# Linesensors.net
KiCad netlist of a schematic drawn in EAGLE
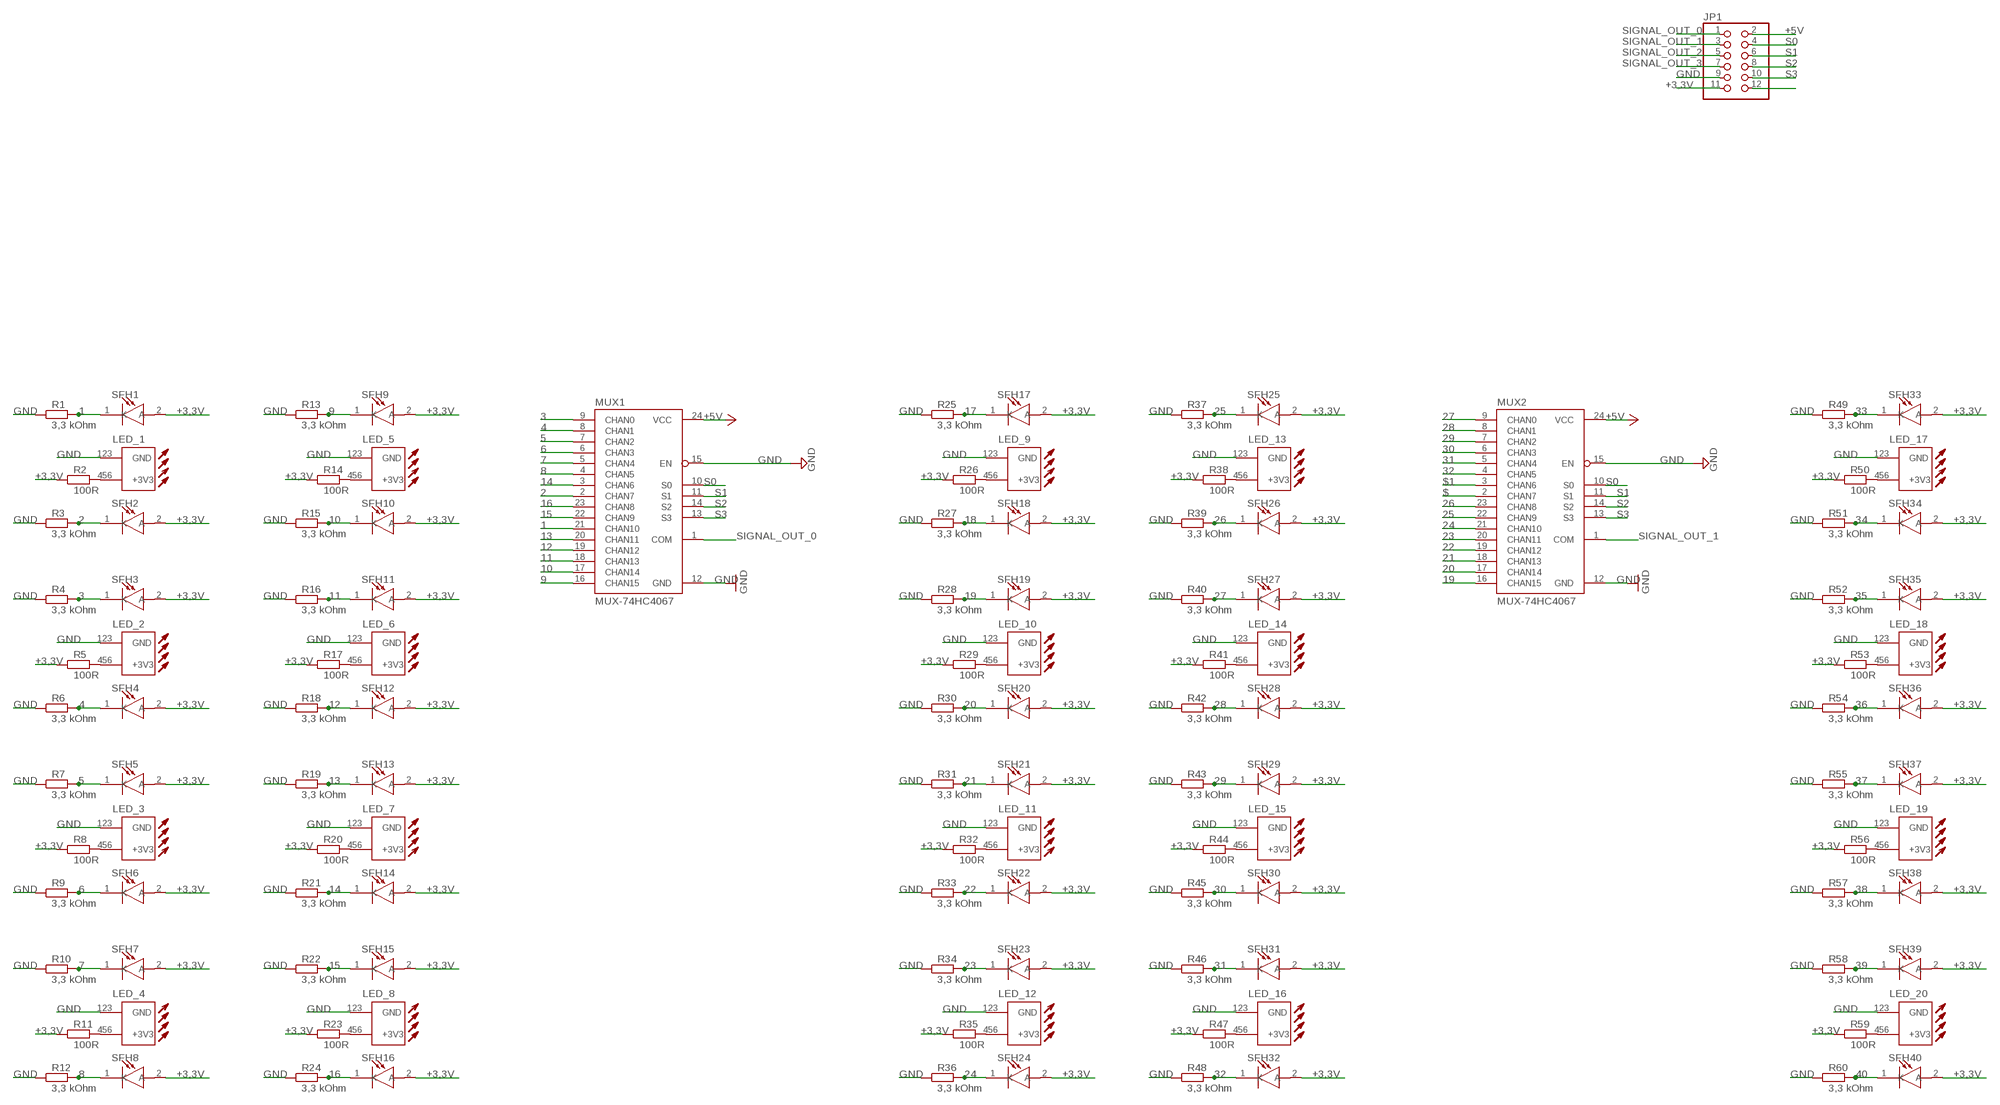
[diagram p0: schematic, sheet 1, part 1 of 2]
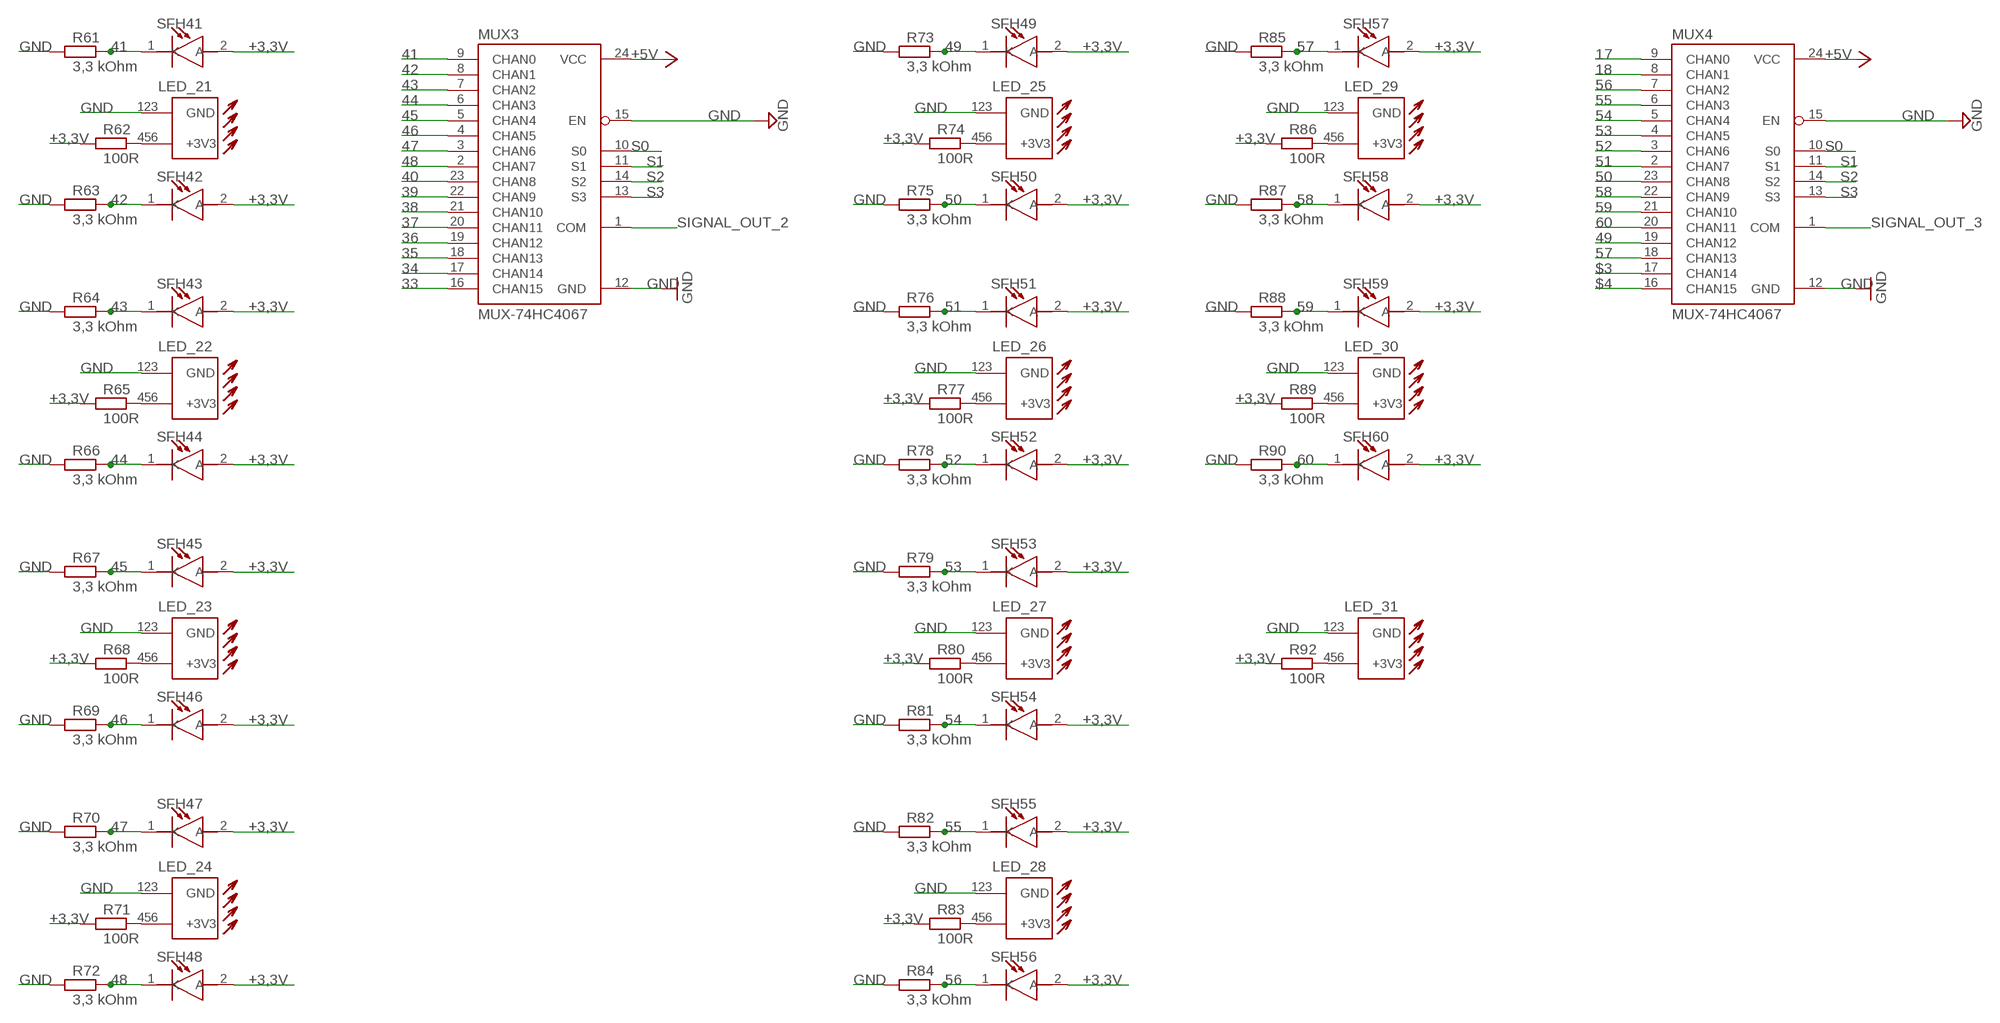
[diagram p1: schematic, sheet 1, part 2 of 2]

(export (version "E")
  (design (tool "Eeschema 10.0.6"))
  (components
    (comp (ref "JP1")
      (value "PINHD-2X6")
      (footprint "eagle-import:2X06")
      (libsource (lib "eagle-import") (part "PINHD-2X6"))
    )
    (comp (ref "LED_1")
      (value "RND135-00056LEDD")
      (footprint "eagle-import:LED")
      (libsource (lib "eagle-import") (part "RND135-00056LEDD"))
    )
    (comp (ref "LED_2")
      (value "RND135-00056LEDD")
      (footprint "eagle-import:LED")
      (libsource (lib "eagle-import") (part "RND135-00056LEDD"))
    )
    (comp (ref "LED_3")
      (value "RND135-00056LEDD")
      (footprint "eagle-import:LED")
      (libsource (lib "eagle-import") (part "RND135-00056LEDD"))
    )
    (comp (ref "LED_4")
      (value "RND135-00056LEDD")
      (footprint "eagle-import:LED")
      (libsource (lib "eagle-import") (part "RND135-00056LEDD"))
    )
    (comp (ref "LED_5")
      (value "RND135-00056LEDD")
      (footprint "eagle-import:LED")
      (libsource (lib "eagle-import") (part "RND135-00056LEDD"))
    )
    (comp (ref "LED_6")
      (value "RND135-00056LEDD")
      (footprint "eagle-import:LED")
      (libsource (lib "eagle-import") (part "RND135-00056LEDD"))
    )
    (comp (ref "LED_7")
      (value "RND135-00056LEDD")
      (footprint "eagle-import:LED")
      (libsource (lib "eagle-import") (part "RND135-00056LEDD"))
    )
    (comp (ref "LED_8")
      (value "RND135-00056LEDD")
      (footprint "eagle-import:LED")
      (libsource (lib "eagle-import") (part "RND135-00056LEDD"))
    )
    (comp (ref "LED_9")
      (value "RND135-00056LEDD")
      (footprint "eagle-import:LED")
      (libsource (lib "eagle-import") (part "RND135-00056LEDD"))
    )
    (comp (ref "LED_10")
      (value "RND135-00056LEDD")
      (footprint "eagle-import:LED")
      (libsource (lib "eagle-import") (part "RND135-00056LEDD"))
    )
    (comp (ref "LED_11")
      (value "RND135-00056LEDD")
      (footprint "eagle-import:LED")
      (libsource (lib "eagle-import") (part "RND135-00056LEDD"))
    )
    (comp (ref "LED_12")
      (value "RND135-00056LEDD")
      (footprint "eagle-import:LED")
      (libsource (lib "eagle-import") (part "RND135-00056LEDD"))
    )
    (comp (ref "LED_13")
      (value "RND135-00056LEDD")
      (footprint "eagle-import:LED")
      (libsource (lib "eagle-import") (part "RND135-00056LEDD"))
    )
    (comp (ref "LED_14")
      (value "RND135-00056LEDD")
      (footprint "eagle-import:LED")
      (libsource (lib "eagle-import") (part "RND135-00056LEDD"))
    )
    (comp (ref "LED_15")
      (value "RND135-00056LEDD")
      (footprint "eagle-import:LED")
      (libsource (lib "eagle-import") (part "RND135-00056LEDD"))
    )
    (comp (ref "LED_16")
      (value "RND135-00056LEDD")
      (footprint "eagle-import:LED")
      (libsource (lib "eagle-import") (part "RND135-00056LEDD"))
    )
    (comp (ref "LED_17")
      (value "RND135-00056LEDD")
      (footprint "eagle-import:LED")
      (libsource (lib "eagle-import") (part "RND135-00056LEDD"))
    )
    (comp (ref "LED_18")
      (value "RND135-00056LEDD")
      (footprint "eagle-import:LED")
      (libsource (lib "eagle-import") (part "RND135-00056LEDD"))
    )
    (comp (ref "LED_19")
      (value "RND135-00056LEDD")
      (footprint "eagle-import:LED")
      (libsource (lib "eagle-import") (part "RND135-00056LEDD"))
    )
    (comp (ref "LED_20")
      (value "RND135-00056LEDD")
      (footprint "eagle-import:LED")
      (libsource (lib "eagle-import") (part "RND135-00056LEDD"))
    )
    (comp (ref "LED_21")
      (value "RND135-00056LEDD")
      (footprint "eagle-import:LED")
      (libsource (lib "eagle-import") (part "RND135-00056LEDD"))
    )
    (comp (ref "LED_22")
      (value "RND135-00056LEDD")
      (footprint "eagle-import:LED")
      (libsource (lib "eagle-import") (part "RND135-00056LEDD"))
    )
    (comp (ref "LED_23")
      (value "RND135-00056LEDD")
      (footprint "eagle-import:LED")
      (libsource (lib "eagle-import") (part "RND135-00056LEDD"))
    )
    (comp (ref "LED_24")
      (value "RND135-00056LEDD")
      (footprint "eagle-import:LED")
      (libsource (lib "eagle-import") (part "RND135-00056LEDD"))
    )
    (comp (ref "LED_25")
      (value "RND135-00056LEDD")
      (footprint "eagle-import:LED")
      (libsource (lib "eagle-import") (part "RND135-00056LEDD"))
    )
    (comp (ref "LED_26")
      (value "RND135-00056LEDD")
      (footprint "eagle-import:LED")
      (libsource (lib "eagle-import") (part "RND135-00056LEDD"))
    )
    (comp (ref "LED_27")
      (value "RND135-00056LEDD")
      (footprint "eagle-import:LED")
      (libsource (lib "eagle-import") (part "RND135-00056LEDD"))
    )
    (comp (ref "LED_28")
      (value "RND135-00056LEDD")
      (footprint "eagle-import:LED")
      (libsource (lib "eagle-import") (part "RND135-00056LEDD"))
    )
    (comp (ref "LED_29")
      (value "RND135-00056LEDD")
      (footprint "eagle-import:LED")
      (libsource (lib "eagle-import") (part "RND135-00056LEDD"))
    )
    (comp (ref "LED_30")
      (value "RND135-00056LEDD")
      (footprint "eagle-import:LED")
      (libsource (lib "eagle-import") (part "RND135-00056LEDD"))
    )
    (comp (ref "LED_31")
      (value "RND135-00056LEDD")
      (footprint "eagle-import:LED")
      (libsource (lib "eagle-import") (part "RND135-00056LEDD"))
    )
    (comp (ref "MUX1")
      (value "MUX-74HC4067")
      (footprint "eagle-import:SSOP24")
      (libsource (lib "eagle-import") (part "MUX-74HC4067SMD"))
    )
    (comp (ref "MUX2")
      (value "MUX-74HC4067")
      (footprint "eagle-import:SSOP24")
      (libsource (lib "eagle-import") (part "MUX-74HC4067SMD"))
    )
    (comp (ref "MUX3")
      (value "MUX-74HC4067")
      (footprint "eagle-import:SSOP24")
      (libsource (lib "eagle-import") (part "MUX-74HC4067SMD"))
    )
    (comp (ref "MUX4")
      (value "MUX-74HC4067")
      (footprint "eagle-import:SSOP24")
      (libsource (lib "eagle-import") (part "MUX-74HC4067SMD"))
    )
    (comp (ref "R1")
      (value "3,3 kOhm")
      (footprint "eagle-import:R1206")
      (libsource (lib "eagle-import") (part "R-EU_R1206"))
    )
    (comp (ref "R2")
      (value "100R")
      (footprint "eagle-import:R1206")
      (libsource (lib "eagle-import") (part "R-EU_R1206"))
    )
    (comp (ref "R3")
      (value "3,3 kOhm")
      (footprint "eagle-import:R1206")
      (libsource (lib "eagle-import") (part "R-EU_R1206"))
    )
    (comp (ref "R4")
      (value "3,3 kOhm")
      (footprint "eagle-import:R1206")
      (libsource (lib "eagle-import") (part "R-EU_R1206"))
    )
    (comp (ref "R5")
      (value "100R")
      (footprint "eagle-import:R1206")
      (libsource (lib "eagle-import") (part "R-EU_R1206"))
    )
    (comp (ref "R6")
      (value "3,3 kOhm")
      (footprint "eagle-import:R1206")
      (libsource (lib "eagle-import") (part "R-EU_R1206"))
    )
    (comp (ref "R7")
      (value "3,3 kOhm")
      (footprint "eagle-import:R1206")
      (libsource (lib "eagle-import") (part "R-EU_R1206"))
    )
    (comp (ref "R8")
      (value "100R")
      (footprint "eagle-import:R1206")
      (libsource (lib "eagle-import") (part "R-EU_R1206"))
    )
    (comp (ref "R9")
      (value "3,3 kOhm")
      (footprint "eagle-import:R1206")
      (libsource (lib "eagle-import") (part "R-EU_R1206"))
    )
    (comp (ref "R10")
      (value "3,3 kOhm")
      (footprint "eagle-import:R1206")
      (libsource (lib "eagle-import") (part "R-EU_R1206"))
    )
    (comp (ref "R11")
      (value "100R")
      (footprint "eagle-import:R1206")
      (libsource (lib "eagle-import") (part "R-EU_R1206"))
    )
    (comp (ref "R12")
      (value "3,3 kOhm")
      (footprint "eagle-import:R1206")
      (libsource (lib "eagle-import") (part "R-EU_R1206"))
    )
    (comp (ref "R13")
      (value "3,3 kOhm")
      (footprint "eagle-import:R1206")
      (libsource (lib "eagle-import") (part "R-EU_R1206"))
    )
    (comp (ref "R14")
      (value "100R")
      (footprint "eagle-import:R1206")
      (libsource (lib "eagle-import") (part "R-EU_R1206"))
    )
    (comp (ref "R15")
      (value "3,3 kOhm")
      (footprint "eagle-import:R1206")
      (libsource (lib "eagle-import") (part "R-EU_R1206"))
    )
    (comp (ref "R16")
      (value "3,3 kOhm")
      (footprint "eagle-import:R1206")
      (libsource (lib "eagle-import") (part "R-EU_R1206"))
    )
    (comp (ref "R17")
      (value "100R")
      (footprint "eagle-import:R1206")
      (libsource (lib "eagle-import") (part "R-EU_R1206"))
    )
    (comp (ref "R18")
      (value "3,3 kOhm")
      (footprint "eagle-import:R1206")
      (libsource (lib "eagle-import") (part "R-EU_R1206"))
    )
    (comp (ref "R19")
      (value "3,3 kOhm")
      (footprint "eagle-import:R1206")
      (libsource (lib "eagle-import") (part "R-EU_R1206"))
    )
    (comp (ref "R20")
      (value "100R")
      (footprint "eagle-import:R1206")
      (libsource (lib "eagle-import") (part "R-EU_R1206"))
    )
    (comp (ref "R21")
      (value "3,3 kOhm")
      (footprint "eagle-import:R1206")
      (libsource (lib "eagle-import") (part "R-EU_R1206"))
    )
    (comp (ref "R22")
      (value "3,3 kOhm")
      (footprint "eagle-import:R1206")
      (libsource (lib "eagle-import") (part "R-EU_R1206"))
    )
    (comp (ref "R23")
      (value "100R")
      (footprint "eagle-import:R1206")
      (libsource (lib "eagle-import") (part "R-EU_R1206"))
    )
    (comp (ref "R24")
      (value "3,3 kOhm")
      (footprint "eagle-import:R1206")
      (libsource (lib "eagle-import") (part "R-EU_R1206"))
    )
    (comp (ref "R25")
      (value "3,3 kOhm")
      (footprint "eagle-import:R1206")
      (libsource (lib "eagle-import") (part "R-EU_R1206"))
    )
    (comp (ref "R26")
      (value "100R")
      (footprint "eagle-import:R1206")
      (libsource (lib "eagle-import") (part "R-EU_R1206"))
    )
    (comp (ref "R27")
      (value "3,3 kOhm")
      (footprint "eagle-import:R1206")
      (libsource (lib "eagle-import") (part "R-EU_R1206"))
    )
    (comp (ref "R28")
      (value "3,3 kOhm")
      (footprint "eagle-import:R1206")
      (libsource (lib "eagle-import") (part "R-EU_R1206"))
    )
    (comp (ref "R29")
      (value "100R")
      (footprint "eagle-import:R1206")
      (libsource (lib "eagle-import") (part "R-EU_R1206"))
    )
    (comp (ref "R30")
      (value "3,3 kOhm")
      (footprint "eagle-import:R1206")
      (libsource (lib "eagle-import") (part "R-EU_R1206"))
    )
    (comp (ref "R31")
      (value "3,3 kOhm")
      (footprint "eagle-import:R1206")
      (libsource (lib "eagle-import") (part "R-EU_R1206"))
    )
    (comp (ref "R32")
      (value "100R")
      (footprint "eagle-import:R1206")
      (libsource (lib "eagle-import") (part "R-EU_R1206"))
    )
    (comp (ref "R33")
      (value "3,3 kOhm")
      (footprint "eagle-import:R1206")
      (libsource (lib "eagle-import") (part "R-EU_R1206"))
    )
    (comp (ref "R34")
      (value "3,3 kOhm")
      (footprint "eagle-import:R1206")
      (libsource (lib "eagle-import") (part "R-EU_R1206"))
    )
    (comp (ref "R35")
      (value "100R")
      (footprint "eagle-import:R1206")
      (libsource (lib "eagle-import") (part "R-EU_R1206"))
    )
    (comp (ref "R36")
      (value "3,3 kOhm")
      (footprint "eagle-import:R1206")
      (libsource (lib "eagle-import") (part "R-EU_R1206"))
    )
    (comp (ref "R37")
      (value "3,3 kOhm")
      (footprint "eagle-import:R1206")
      (libsource (lib "eagle-import") (part "R-EU_R1206"))
    )
    (comp (ref "R38")
      (value "100R")
      (footprint "eagle-import:R1206")
      (libsource (lib "eagle-import") (part "R-EU_R1206"))
    )
    (comp (ref "R39")
      (value "3,3 kOhm")
      (footprint "eagle-import:R1206")
      (libsource (lib "eagle-import") (part "R-EU_R1206"))
    )
    (comp (ref "R40")
      (value "3,3 kOhm")
      (footprint "eagle-import:R1206")
      (libsource (lib "eagle-import") (part "R-EU_R1206"))
    )
    (comp (ref "R41")
      (value "100R")
      (footprint "eagle-import:R1206")
      (libsource (lib "eagle-import") (part "R-EU_R1206"))
    )
    (comp (ref "R42")
      (value "3,3 kOhm")
      (footprint "eagle-import:R1206")
      (libsource (lib "eagle-import") (part "R-EU_R1206"))
    )
    (comp (ref "R43")
      (value "3,3 kOhm")
      (footprint "eagle-import:R1206")
      (libsource (lib "eagle-import") (part "R-EU_R1206"))
    )
    (comp (ref "R44")
      (value "100R")
      (footprint "eagle-import:R1206")
      (libsource (lib "eagle-import") (part "R-EU_R1206"))
    )
    (comp (ref "R45")
      (value "3,3 kOhm")
      (footprint "eagle-import:R1206")
      (libsource (lib "eagle-import") (part "R-EU_R1206"))
    )
    (comp (ref "R46")
      (value "3,3 kOhm")
      (footprint "eagle-import:R1206")
      (libsource (lib "eagle-import") (part "R-EU_R1206"))
    )
    (comp (ref "R47")
      (value "100R")
      (footprint "eagle-import:R1206")
      (libsource (lib "eagle-import") (part "R-EU_R1206"))
    )
    (comp (ref "R48")
      (value "3,3 kOhm")
      (footprint "eagle-import:R1206")
      (libsource (lib "eagle-import") (part "R-EU_R1206"))
    )
    (comp (ref "R49")
      (value "3,3 kOhm")
      (footprint "eagle-import:R1206")
      (libsource (lib "eagle-import") (part "R-EU_R1206"))
    )
    (comp (ref "R50")
      (value "100R")
      (footprint "eagle-import:R1206")
      (libsource (lib "eagle-import") (part "R-EU_R1206"))
    )
    (comp (ref "R51")
      (value "3,3 kOhm")
      (footprint "eagle-import:R1206")
      (libsource (lib "eagle-import") (part "R-EU_R1206"))
    )
    (comp (ref "R52")
      (value "3,3 kOhm")
      (footprint "eagle-import:R1206")
      (libsource (lib "eagle-import") (part "R-EU_R1206"))
    )
    (comp (ref "R53")
      (value "100R")
      (footprint "eagle-import:R1206")
      (libsource (lib "eagle-import") (part "R-EU_R1206"))
    )
    (comp (ref "R54")
      (value "3,3 kOhm")
      (footprint "eagle-import:R1206")
      (libsource (lib "eagle-import") (part "R-EU_R1206"))
    )
    (comp (ref "R55")
      (value "3,3 kOhm")
      (footprint "eagle-import:R1206")
      (libsource (lib "eagle-import") (part "R-EU_R1206"))
    )
    (comp (ref "R56")
      (value "100R")
      (footprint "eagle-import:R1206")
      (libsource (lib "eagle-import") (part "R-EU_R1206"))
    )
    (comp (ref "R57")
      (value "3,3 kOhm")
      (footprint "eagle-import:R1206")
      (libsource (lib "eagle-import") (part "R-EU_R1206"))
    )
    (comp (ref "R58")
      (value "3,3 kOhm")
      (footprint "eagle-import:R1206")
      (libsource (lib "eagle-import") (part "R-EU_R1206"))
    )
    (comp (ref "R59")
      (value "100R")
      (footprint "eagle-import:R1206")
      (libsource (lib "eagle-import") (part "R-EU_R1206"))
    )
    (comp (ref "R60")
      (value "3,3 kOhm")
      (footprint "eagle-import:R1206")
      (libsource (lib "eagle-import") (part "R-EU_R1206"))
    )
    (comp (ref "R61")
      (value "3,3 kOhm")
      (footprint "eagle-import:R1206")
      (libsource (lib "eagle-import") (part "R-EU_R1206"))
    )
    (comp (ref "R62")
      (value "100R")
      (footprint "eagle-import:R1206")
      (libsource (lib "eagle-import") (part "R-EU_R1206"))
    )
    (comp (ref "R63")
      (value "3,3 kOhm")
      (footprint "eagle-import:R1206")
      (libsource (lib "eagle-import") (part "R-EU_R1206"))
    )
    (comp (ref "R64")
      (value "3,3 kOhm")
      (footprint "eagle-import:R1206")
      (libsource (lib "eagle-import") (part "R-EU_R1206"))
    )
    (comp (ref "R65")
      (value "100R")
      (footprint "eagle-import:R1206")
      (libsource (lib "eagle-import") (part "R-EU_R1206"))
    )
    (comp (ref "R66")
      (value "3,3 kOhm")
      (footprint "eagle-import:R1206")
      (libsource (lib "eagle-import") (part "R-EU_R1206"))
    )
    (comp (ref "R67")
      (value "3,3 kOhm")
      (footprint "eagle-import:R1206")
      (libsource (lib "eagle-import") (part "R-EU_R1206"))
    )
    (comp (ref "R68")
      (value "100R")
      (footprint "eagle-import:R1206")
      (libsource (lib "eagle-import") (part "R-EU_R1206"))
    )
    (comp (ref "R69")
      (value "3,3 kOhm")
      (footprint "eagle-import:R1206")
      (libsource (lib "eagle-import") (part "R-EU_R1206"))
    )
    (comp (ref "R70")
      (value "3,3 kOhm")
      (footprint "eagle-import:R1206")
      (libsource (lib "eagle-import") (part "R-EU_R1206"))
    )
    (comp (ref "R71")
      (value "100R")
      (footprint "eagle-import:R1206")
      (libsource (lib "eagle-import") (part "R-EU_R1206"))
    )
    (comp (ref "R72")
      (value "3,3 kOhm")
      (footprint "eagle-import:R1206")
      (libsource (lib "eagle-import") (part "R-EU_R1206"))
    )
    (comp (ref "R73")
      (value "3,3 kOhm")
      (footprint "eagle-import:R1206")
      (libsource (lib "eagle-import") (part "R-EU_R1206"))
    )
    (comp (ref "R74")
      (value "100R")
      (footprint "eagle-import:R1206")
      (libsource (lib "eagle-import") (part "R-EU_R1206"))
    )
    (comp (ref "R75")
      (value "3,3 kOhm")
      (footprint "eagle-import:R1206")
      (libsource (lib "eagle-import") (part "R-EU_R1206"))
    )
    (comp (ref "R76")
      (value "3,3 kOhm")
      (footprint "eagle-import:R1206")
      (libsource (lib "eagle-import") (part "R-EU_R1206"))
    )
    (comp (ref "R77")
      (value "100R")
      (footprint "eagle-import:R1206")
      (libsource (lib "eagle-import") (part "R-EU_R1206"))
    )
    (comp (ref "R78")
      (value "3,3 kOhm")
      (footprint "eagle-import:R1206")
      (libsource (lib "eagle-import") (part "R-EU_R1206"))
    )
    (comp (ref "R79")
      (value "3,3 kOhm")
      (footprint "eagle-import:R1206")
      (libsource (lib "eagle-import") (part "R-EU_R1206"))
    )
    (comp (ref "R80")
      (value "100R")
      (footprint "eagle-import:R1206")
      (libsource (lib "eagle-import") (part "R-EU_R1206"))
    )
    (comp (ref "R81")
      (value "3,3 kOhm")
      (footprint "eagle-import:R1206")
      (libsource (lib "eagle-import") (part "R-EU_R1206"))
    )
    (comp (ref "R82")
      (value "3,3 kOhm")
      (footprint "eagle-import:R1206")
      (libsource (lib "eagle-import") (part "R-EU_R1206"))
    )
    (comp (ref "R83")
      (value "100R")
      (footprint "eagle-import:R1206")
      (libsource (lib "eagle-import") (part "R-EU_R1206"))
    )
    (comp (ref "R84")
      (value "3,3 kOhm")
      (footprint "eagle-import:R1206")
      (libsource (lib "eagle-import") (part "R-EU_R1206"))
    )
    (comp (ref "R85")
      (value "3,3 kOhm")
      (footprint "eagle-import:R1206")
      (libsource (lib "eagle-import") (part "R-EU_R1206"))
    )
    (comp (ref "R86")
      (value "100R")
      (footprint "eagle-import:R1206")
      (libsource (lib "eagle-import") (part "R-EU_R1206"))
    )
    (comp (ref "R87")
      (value "3,3 kOhm")
      (footprint "eagle-import:R1206")
      (libsource (lib "eagle-import") (part "R-EU_R1206"))
    )
    (comp (ref "R88")
      (value "3,3 kOhm")
      (footprint "eagle-import:R1206")
      (libsource (lib "eagle-import") (part "R-EU_R1206"))
    )
    (comp (ref "R89")
      (value "100R")
      (footprint "eagle-import:R1206")
      (libsource (lib "eagle-import") (part "R-EU_R1206"))
    )
    (comp (ref "R90")
      (value "3,3 kOhm")
      (footprint "eagle-import:R1206")
      (libsource (lib "eagle-import") (part "R-EU_R1206"))
    )
    (comp (ref "R92")
      (value "100R")
      (footprint "eagle-import:R1206")
      (libsource (lib "eagle-import") (part "R-EU_R1206"))
    )
    (comp (ref "SFH1")
      (value "SFH_3716")
      (footprint "eagle-import:LEDC2012X89N")
      (fields
        (field (name "MANUFACTURER_PART_NUMBER") "SFH 3716")
        (field (name "MOUSER_PART_NUMBER") "720-SFH3716")
        (field (name "RS_PART_NUMBER") "1115952P")
      )
      (libsource (lib "eagle-import") (part "SFH_3716"))
    )
    (comp (ref "SFH2")
      (value "SFH_3716")
      (footprint "eagle-import:LEDC2012X89N")
      (fields
        (field (name "MANUFACTURER_PART_NUMBER") "SFH 3716")
        (field (name "MOUSER_PART_NUMBER") "720-SFH3716")
        (field (name "RS_PART_NUMBER") "1115952P")
      )
      (libsource (lib "eagle-import") (part "SFH_3716"))
    )
    (comp (ref "SFH3")
      (value "SFH_3716")
      (footprint "eagle-import:LEDC2012X89N")
      (fields
        (field (name "MANUFACTURER_PART_NUMBER") "SFH 3716")
        (field (name "MOUSER_PART_NUMBER") "720-SFH3716")
        (field (name "RS_PART_NUMBER") "1115952P")
      )
      (libsource (lib "eagle-import") (part "SFH_3716"))
    )
    (comp (ref "SFH4")
      (value "SFH_3716")
      (footprint "eagle-import:LEDC2012X89N")
      (fields
        (field (name "MANUFACTURER_PART_NUMBER") "SFH 3716")
        (field (name "MOUSER_PART_NUMBER") "720-SFH3716")
        (field (name "RS_PART_NUMBER") "1115952P")
      )
      (libsource (lib "eagle-import") (part "SFH_3716"))
    )
    (comp (ref "SFH5")
      (value "SFH_3716")
      (footprint "eagle-import:LEDC2012X89N")
      (fields
        (field (name "MANUFACTURER_PART_NUMBER") "SFH 3716")
        (field (name "MOUSER_PART_NUMBER") "720-SFH3716")
        (field (name "RS_PART_NUMBER") "1115952P")
      )
      (libsource (lib "eagle-import") (part "SFH_3716"))
    )
    (comp (ref "SFH6")
      (value "SFH_3716")
      (footprint "eagle-import:LEDC2012X89N")
      (fields
        (field (name "MANUFACTURER_PART_NUMBER") "SFH 3716")
        (field (name "MOUSER_PART_NUMBER") "720-SFH3716")
        (field (name "RS_PART_NUMBER") "1115952P")
      )
      (libsource (lib "eagle-import") (part "SFH_3716"))
    )
    (comp (ref "SFH7")
      (value "SFH_3716")
      (footprint "eagle-import:LEDC2012X89N")
      (fields
        (field (name "MANUFACTURER_PART_NUMBER") "SFH 3716")
        (field (name "MOUSER_PART_NUMBER") "720-SFH3716")
        (field (name "RS_PART_NUMBER") "1115952P")
      )
      (libsource (lib "eagle-import") (part "SFH_3716"))
    )
    (comp (ref "SFH8")
      (value "SFH_3716")
      (footprint "eagle-import:LEDC2012X89N")
      (fields
        (field (name "MANUFACTURER_PART_NUMBER") "SFH 3716")
        (field (name "MOUSER_PART_NUMBER") "720-SFH3716")
        (field (name "RS_PART_NUMBER") "1115952P")
      )
      (libsource (lib "eagle-import") (part "SFH_3716"))
    )
    (comp (ref "SFH9")
      (value "SFH_3716")
      (footprint "eagle-import:LEDC2012X89N")
      (fields
        (field (name "MANUFACTURER_PART_NUMBER") "SFH 3716")
        (field (name "MOUSER_PART_NUMBER") "720-SFH3716")
        (field (name "RS_PART_NUMBER") "1115952P")
      )
      (libsource (lib "eagle-import") (part "SFH_3716"))
    )
    (comp (ref "SFH10")
      (value "SFH_3716")
      (footprint "eagle-import:LEDC2012X89N")
      (fields
        (field (name "MANUFACTURER_PART_NUMBER") "SFH 3716")
        (field (name "MOUSER_PART_NUMBER") "720-SFH3716")
        (field (name "RS_PART_NUMBER") "1115952P")
      )
      (libsource (lib "eagle-import") (part "SFH_3716"))
    )
    (comp (ref "SFH11")
      (value "SFH_3716")
      (footprint "eagle-import:LEDC2012X89N")
      (fields
        (field (name "MANUFACTURER_PART_NUMBER") "SFH 3716")
        (field (name "MOUSER_PART_NUMBER") "720-SFH3716")
        (field (name "RS_PART_NUMBER") "1115952P")
      )
      (libsource (lib "eagle-import") (part "SFH_3716"))
    )
    (comp (ref "SFH12")
      (value "SFH_3716")
      (footprint "eagle-import:LEDC2012X89N")
      (fields
        (field (name "MANUFACTURER_PART_NUMBER") "SFH 3716")
        (field (name "MOUSER_PART_NUMBER") "720-SFH3716")
        (field (name "RS_PART_NUMBER") "1115952P")
      )
      (libsource (lib "eagle-import") (part "SFH_3716"))
    )
    (comp (ref "SFH13")
      (value "SFH_3716")
      (footprint "eagle-import:LEDC2012X89N")
      (fields
        (field (name "MANUFACTURER_PART_NUMBER") "SFH 3716")
        (field (name "MOUSER_PART_NUMBER") "720-SFH3716")
        (field (name "RS_PART_NUMBER") "1115952P")
      )
      (libsource (lib "eagle-import") (part "SFH_3716"))
    )
    (comp (ref "SFH14")
      (value "SFH_3716")
      (footprint "eagle-import:LEDC2012X89N")
      (fields
        (field (name "MANUFACTURER_PART_NUMBER") "SFH 3716")
        (field (name "MOUSER_PART_NUMBER") "720-SFH3716")
        (field (name "RS_PART_NUMBER") "1115952P")
      )
      (libsource (lib "eagle-import") (part "SFH_3716"))
    )
    (comp (ref "SFH15")
      (value "SFH_3716")
      (footprint "eagle-import:LEDC2012X89N")
      (fields
        (field (name "MANUFACTURER_PART_NUMBER") "SFH 3716")
        (field (name "MOUSER_PART_NUMBER") "720-SFH3716")
        (field (name "RS_PART_NUMBER") "1115952P")
      )
      (libsource (lib "eagle-import") (part "SFH_3716"))
    )
    (comp (ref "SFH16")
      (value "SFH_3716")
      (footprint "eagle-import:LEDC2012X89N")
      (fields
        (field (name "MANUFACTURER_PART_NUMBER") "SFH 3716")
        (field (name "MOUSER_PART_NUMBER") "720-SFH3716")
        (field (name "RS_PART_NUMBER") "1115952P")
      )
      (libsource (lib "eagle-import") (part "SFH_3716"))
    )
    (comp (ref "SFH17")
      (value "SFH_3716")
      (footprint "eagle-import:LEDC2012X89N")
      (fields
        (field (name "MANUFACTURER_PART_NUMBER") "SFH 3716")
        (field (name "MOUSER_PART_NUMBER") "720-SFH3716")
        (field (name "RS_PART_NUMBER") "1115952P")
      )
      (libsource (lib "eagle-import") (part "SFH_3716"))
    )
    (comp (ref "SFH18")
      (value "SFH_3716")
      (footprint "eagle-import:LEDC2012X89N")
      (fields
        (field (name "MANUFACTURER_PART_NUMBER") "SFH 3716")
        (field (name "MOUSER_PART_NUMBER") "720-SFH3716")
        (field (name "RS_PART_NUMBER") "1115952P")
      )
      (libsource (lib "eagle-import") (part "SFH_3716"))
    )
    (comp (ref "SFH19")
      (value "SFH_3716")
      (footprint "eagle-import:LEDC2012X89N")
      (fields
        (field (name "MANUFACTURER_PART_NUMBER") "SFH 3716")
        (field (name "MOUSER_PART_NUMBER") "720-SFH3716")
        (field (name "RS_PART_NUMBER") "1115952P")
      )
      (libsource (lib "eagle-import") (part "SFH_3716"))
    )
    (comp (ref "SFH20")
      (value "SFH_3716")
      (footprint "eagle-import:LEDC2012X89N")
      (fields
        (field (name "MANUFACTURER_PART_NUMBER") "SFH 3716")
        (field (name "MOUSER_PART_NUMBER") "720-SFH3716")
        (field (name "RS_PART_NUMBER") "1115952P")
      )
      (libsource (lib "eagle-import") (part "SFH_3716"))
    )
    (comp (ref "SFH21")
      (value "SFH_3716")
      (footprint "eagle-import:LEDC2012X89N")
      (fields
        (field (name "MANUFACTURER_PART_NUMBER") "SFH 3716")
        (field (name "MOUSER_PART_NUMBER") "720-SFH3716")
        (field (name "RS_PART_NUMBER") "1115952P")
      )
      (libsource (lib "eagle-import") (part "SFH_3716"))
    )
    (comp (ref "SFH22")
      (value "SFH_3716")
      (footprint "eagle-import:LEDC2012X89N")
      (fields
        (field (name "MANUFACTURER_PART_NUMBER") "SFH 3716")
        (field (name "MOUSER_PART_NUMBER") "720-SFH3716")
        (field (name "RS_PART_NUMBER") "1115952P")
      )
      (libsource (lib "eagle-import") (part "SFH_3716"))
    )
    (comp (ref "SFH23")
      (value "SFH_3716")
      (footprint "eagle-import:LEDC2012X89N")
      (fields
        (field (name "MANUFACTURER_PART_NUMBER") "SFH 3716")
        (field (name "MOUSER_PART_NUMBER") "720-SFH3716")
        (field (name "RS_PART_NUMBER") "1115952P")
      )
      (libsource (lib "eagle-import") (part "SFH_3716"))
    )
    (comp (ref "SFH24")
      (value "SFH_3716")
      (footprint "eagle-import:LEDC2012X89N")
      (fields
        (field (name "MANUFACTURER_PART_NUMBER") "SFH 3716")
        (field (name "MOUSER_PART_NUMBER") "720-SFH3716")
        (field (name "RS_PART_NUMBER") "1115952P")
      )
      (libsource (lib "eagle-import") (part "SFH_3716"))
    )
    (comp (ref "SFH25")
      (value "SFH_3716")
      (footprint "eagle-import:LEDC2012X89N")
      (fields
        (field (name "MANUFACTURER_PART_NUMBER") "SFH 3716")
        (field (name "MOUSER_PART_NUMBER") "720-SFH3716")
        (field (name "RS_PART_NUMBER") "1115952P")
      )
      (libsource (lib "eagle-import") (part "SFH_3716"))
    )
    (comp (ref "SFH26")
      (value "SFH_3716")
      (footprint "eagle-import:LEDC2012X89N")
      (fields
        (field (name "MANUFACTURER_PART_NUMBER") "SFH 3716")
        (field (name "MOUSER_PART_NUMBER") "720-SFH3716")
        (field (name "RS_PART_NUMBER") "1115952P")
      )
      (libsource (lib "eagle-import") (part "SFH_3716"))
    )
    (comp (ref "SFH27")
      (value "SFH_3716")
      (footprint "eagle-import:LEDC2012X89N")
      (fields
        (field (name "MANUFACTURER_PART_NUMBER") "SFH 3716")
        (field (name "MOUSER_PART_NUMBER") "720-SFH3716")
        (field (name "RS_PART_NUMBER") "1115952P")
      )
      (libsource (lib "eagle-import") (part "SFH_3716"))
    )
    (comp (ref "SFH28")
      (value "SFH_3716")
      (footprint "eagle-import:LEDC2012X89N")
      (fields
        (field (name "MANUFACTURER_PART_NUMBER") "SFH 3716")
        (field (name "MOUSER_PART_NUMBER") "720-SFH3716")
        (field (name "RS_PART_NUMBER") "1115952P")
      )
      (libsource (lib "eagle-import") (part "SFH_3716"))
    )
    (comp (ref "SFH29")
      (value "SFH_3716")
      (footprint "eagle-import:LEDC2012X89N")
      (fields
        (field (name "MANUFACTURER_PART_NUMBER") "SFH 3716")
        (field (name "MOUSER_PART_NUMBER") "720-SFH3716")
        (field (name "RS_PART_NUMBER") "1115952P")
      )
      (libsource (lib "eagle-import") (part "SFH_3716"))
    )
    (comp (ref "SFH30")
      (value "SFH_3716")
      (footprint "eagle-import:LEDC2012X89N")
      (fields
        (field (name "MANUFACTURER_PART_NUMBER") "SFH 3716")
        (field (name "MOUSER_PART_NUMBER") "720-SFH3716")
        (field (name "RS_PART_NUMBER") "1115952P")
      )
      (libsource (lib "eagle-import") (part "SFH_3716"))
    )
    (comp (ref "SFH31")
      (value "SFH_3716")
      (footprint "eagle-import:LEDC2012X89N")
      (fields
        (field (name "MANUFACTURER_PART_NUMBER") "SFH 3716")
        (field (name "MOUSER_PART_NUMBER") "720-SFH3716")
        (field (name "RS_PART_NUMBER") "1115952P")
      )
      (libsource (lib "eagle-import") (part "SFH_3716"))
    )
    (comp (ref "SFH32")
      (value "SFH_3716")
      (footprint "eagle-import:LEDC2012X89N")
      (fields
        (field (name "MANUFACTURER_PART_NUMBER") "SFH 3716")
        (field (name "MOUSER_PART_NUMBER") "720-SFH3716")
        (field (name "RS_PART_NUMBER") "1115952P")
      )
      (libsource (lib "eagle-import") (part "SFH_3716"))
    )
    (comp (ref "SFH33")
      (value "SFH_3716")
      (footprint "eagle-import:LEDC2012X89N")
      (fields
        (field (name "MANUFACTURER_PART_NUMBER") "SFH 3716")
        (field (name "MOUSER_PART_NUMBER") "720-SFH3716")
        (field (name "RS_PART_NUMBER") "1115952P")
      )
      (libsource (lib "eagle-import") (part "SFH_3716"))
    )
    (comp (ref "SFH34")
      (value "SFH_3716")
      (footprint "eagle-import:LEDC2012X89N")
      (fields
        (field (name "MANUFACTURER_PART_NUMBER") "SFH 3716")
        (field (name "MOUSER_PART_NUMBER") "720-SFH3716")
        (field (name "RS_PART_NUMBER") "1115952P")
      )
      (libsource (lib "eagle-import") (part "SFH_3716"))
    )
    (comp (ref "SFH35")
      (value "SFH_3716")
      (footprint "eagle-import:LEDC2012X89N")
      (fields
        (field (name "MANUFACTURER_PART_NUMBER") "SFH 3716")
        (field (name "MOUSER_PART_NUMBER") "720-SFH3716")
        (field (name "RS_PART_NUMBER") "1115952P")
      )
      (libsource (lib "eagle-import") (part "SFH_3716"))
    )
    (comp (ref "SFH36")
      (value "SFH_3716")
      (footprint "eagle-import:LEDC2012X89N")
      (fields
        (field (name "MANUFACTURER_PART_NUMBER") "SFH 3716")
        (field (name "MOUSER_PART_NUMBER") "720-SFH3716")
        (field (name "RS_PART_NUMBER") "1115952P")
      )
      (libsource (lib "eagle-import") (part "SFH_3716"))
    )
    (comp (ref "SFH37")
      (value "SFH_3716")
      (footprint "eagle-import:LEDC2012X89N")
      (fields
        (field (name "MANUFACTURER_PART_NUMBER") "SFH 3716")
        (field (name "MOUSER_PART_NUMBER") "720-SFH3716")
        (field (name "RS_PART_NUMBER") "1115952P")
      )
      (libsource (lib "eagle-import") (part "SFH_3716"))
    )
    (comp (ref "SFH38")
      (value "SFH_3716")
      (footprint "eagle-import:LEDC2012X89N")
      (fields
        (field (name "MANUFACTURER_PART_NUMBER") "SFH 3716")
        (field (name "MOUSER_PART_NUMBER") "720-SFH3716")
        (field (name "RS_PART_NUMBER") "1115952P")
      )
      (libsource (lib "eagle-import") (part "SFH_3716"))
    )
    (comp (ref "SFH39")
      (value "SFH_3716")
      (footprint "eagle-import:LEDC2012X89N")
      (fields
        (field (name "MANUFACTURER_PART_NUMBER") "SFH 3716")
        (field (name "MOUSER_PART_NUMBER") "720-SFH3716")
        (field (name "RS_PART_NUMBER") "1115952P")
      )
      (libsource (lib "eagle-import") (part "SFH_3716"))
    )
    (comp (ref "SFH40")
      (value "SFH_3716")
      (footprint "eagle-import:LEDC2012X89N")
      (fields
        (field (name "MANUFACTURER_PART_NUMBER") "SFH 3716")
        (field (name "MOUSER_PART_NUMBER") "720-SFH3716")
        (field (name "RS_PART_NUMBER") "1115952P")
      )
      (libsource (lib "eagle-import") (part "SFH_3716"))
    )
    (comp (ref "SFH41")
      (value "SFH_3716")
      (footprint "eagle-import:LEDC2012X89N")
      (fields
        (field (name "MANUFACTURER_PART_NUMBER") "SFH 3716")
        (field (name "MOUSER_PART_NUMBER") "720-SFH3716")
        (field (name "RS_PART_NUMBER") "1115952P")
      )
      (libsource (lib "eagle-import") (part "SFH_3716"))
    )
    (comp (ref "SFH42")
      (value "SFH_3716")
      (footprint "eagle-import:LEDC2012X89N")
      (fields
        (field (name "MANUFACTURER_PART_NUMBER") "SFH 3716")
        (field (name "MOUSER_PART_NUMBER") "720-SFH3716")
        (field (name "RS_PART_NUMBER") "1115952P")
      )
      (libsource (lib "eagle-import") (part "SFH_3716"))
    )
    (comp (ref "SFH43")
      (value "SFH_3716")
      (footprint "eagle-import:LEDC2012X89N")
      (fields
        (field (name "MANUFACTURER_PART_NUMBER") "SFH 3716")
        (field (name "MOUSER_PART_NUMBER") "720-SFH3716")
        (field (name "RS_PART_NUMBER") "1115952P")
      )
      (libsource (lib "eagle-import") (part "SFH_3716"))
    )
    (comp (ref "SFH44")
      (value "SFH_3716")
      (footprint "eagle-import:LEDC2012X89N")
      (fields
        (field (name "MANUFACTURER_PART_NUMBER") "SFH 3716")
        (field (name "MOUSER_PART_NUMBER") "720-SFH3716")
        (field (name "RS_PART_NUMBER") "1115952P")
      )
      (libsource (lib "eagle-import") (part "SFH_3716"))
    )
    (comp (ref "SFH45")
      (value "SFH_3716")
      (footprint "eagle-import:LEDC2012X89N")
      (fields
        (field (name "MANUFACTURER_PART_NUMBER") "SFH 3716")
        (field (name "MOUSER_PART_NUMBER") "720-SFH3716")
        (field (name "RS_PART_NUMBER") "1115952P")
      )
      (libsource (lib "eagle-import") (part "SFH_3716"))
    )
    (comp (ref "SFH46")
      (value "SFH_3716")
      (footprint "eagle-import:LEDC2012X89N")
      (fields
        (field (name "MANUFACTURER_PART_NUMBER") "SFH 3716")
        (field (name "MOUSER_PART_NUMBER") "720-SFH3716")
        (field (name "RS_PART_NUMBER") "1115952P")
      )
      (libsource (lib "eagle-import") (part "SFH_3716"))
    )
    (comp (ref "SFH47")
      (value "SFH_3716")
      (footprint "eagle-import:LEDC2012X89N")
      (fields
        (field (name "MANUFACTURER_PART_NUMBER") "SFH 3716")
        (field (name "MOUSER_PART_NUMBER") "720-SFH3716")
        (field (name "RS_PART_NUMBER") "1115952P")
      )
      (libsource (lib "eagle-import") (part "SFH_3716"))
    )
    (comp (ref "SFH48")
      (value "SFH_3716")
      (footprint "eagle-import:LEDC2012X89N")
      (fields
        (field (name "MANUFACTURER_PART_NUMBER") "SFH 3716")
        (field (name "MOUSER_PART_NUMBER") "720-SFH3716")
        (field (name "RS_PART_NUMBER") "1115952P")
      )
      (libsource (lib "eagle-import") (part "SFH_3716"))
    )
    (comp (ref "SFH49")
      (value "SFH_3716")
      (footprint "eagle-import:LEDC2012X89N")
      (fields
        (field (name "MANUFACTURER_PART_NUMBER") "SFH 3716")
        (field (name "MOUSER_PART_NUMBER") "720-SFH3716")
        (field (name "RS_PART_NUMBER") "1115952P")
      )
      (libsource (lib "eagle-import") (part "SFH_3716"))
    )
    (comp (ref "SFH50")
      (value "SFH_3716")
      (footprint "eagle-import:LEDC2012X89N")
      (fields
        (field (name "MANUFACTURER_PART_NUMBER") "SFH 3716")
        (field (name "MOUSER_PART_NUMBER") "720-SFH3716")
        (field (name "RS_PART_NUMBER") "1115952P")
      )
      (libsource (lib "eagle-import") (part "SFH_3716"))
    )
    (comp (ref "SFH51")
      (value "SFH_3716")
      (footprint "eagle-import:LEDC2012X89N")
      (fields
        (field (name "MANUFACTURER_PART_NUMBER") "SFH 3716")
        (field (name "MOUSER_PART_NUMBER") "720-SFH3716")
        (field (name "RS_PART_NUMBER") "1115952P")
      )
      (libsource (lib "eagle-import") (part "SFH_3716"))
    )
    (comp (ref "SFH52")
      (value "SFH_3716")
      (footprint "eagle-import:LEDC2012X89N")
      (fields
        (field (name "MANUFACTURER_PART_NUMBER") "SFH 3716")
        (field (name "MOUSER_PART_NUMBER") "720-SFH3716")
        (field (name "RS_PART_NUMBER") "1115952P")
      )
      (libsource (lib "eagle-import") (part "SFH_3716"))
    )
    (comp (ref "SFH53")
      (value "SFH_3716")
      (footprint "eagle-import:LEDC2012X89N")
      (fields
        (field (name "MANUFACTURER_PART_NUMBER") "SFH 3716")
        (field (name "MOUSER_PART_NUMBER") "720-SFH3716")
        (field (name "RS_PART_NUMBER") "1115952P")
      )
      (libsource (lib "eagle-import") (part "SFH_3716"))
    )
    (comp (ref "SFH54")
      (value "SFH_3716")
      (footprint "eagle-import:LEDC2012X89N")
      (fields
        (field (name "MANUFACTURER_PART_NUMBER") "SFH 3716")
        (field (name "MOUSER_PART_NUMBER") "720-SFH3716")
        (field (name "RS_PART_NUMBER") "1115952P")
      )
      (libsource (lib "eagle-import") (part "SFH_3716"))
    )
    (comp (ref "SFH55")
      (value "SFH_3716")
      (footprint "eagle-import:LEDC2012X89N")
      (fields
        (field (name "MANUFACTURER_PART_NUMBER") "SFH 3716")
        (field (name "MOUSER_PART_NUMBER") "720-SFH3716")
        (field (name "RS_PART_NUMBER") "1115952P")
      )
      (libsource (lib "eagle-import") (part "SFH_3716"))
    )
    (comp (ref "SFH56")
      (value "SFH_3716")
      (footprint "eagle-import:LEDC2012X89N")
      (fields
        (field (name "MANUFACTURER_PART_NUMBER") "SFH 3716")
        (field (name "MOUSER_PART_NUMBER") "720-SFH3716")
        (field (name "RS_PART_NUMBER") "1115952P")
      )
      (libsource (lib "eagle-import") (part "SFH_3716"))
    )
    (comp (ref "SFH57")
      (value "SFH_3716")
      (footprint "eagle-import:LEDC2012X89N")
      (fields
        (field (name "MANUFACTURER_PART_NUMBER") "SFH 3716")
        (field (name "MOUSER_PART_NUMBER") "720-SFH3716")
        (field (name "RS_PART_NUMBER") "1115952P")
      )
      (libsource (lib "eagle-import") (part "SFH_3716"))
    )
    (comp (ref "SFH58")
      (value "SFH_3716")
      (footprint "eagle-import:LEDC2012X89N")
      (fields
        (field (name "MANUFACTURER_PART_NUMBER") "SFH 3716")
        (field (name "MOUSER_PART_NUMBER") "720-SFH3716")
        (field (name "RS_PART_NUMBER") "1115952P")
      )
      (libsource (lib "eagle-import") (part "SFH_3716"))
    )
    (comp (ref "SFH59")
      (value "SFH_3716")
      (footprint "eagle-import:LEDC2012X89N")
      (fields
        (field (name "MANUFACTURER_PART_NUMBER") "SFH 3716")
        (field (name "MOUSER_PART_NUMBER") "720-SFH3716")
        (field (name "RS_PART_NUMBER") "1115952P")
      )
      (libsource (lib "eagle-import") (part "SFH_3716"))
    )
    (comp (ref "SFH60")
      (value "SFH_3716")
      (footprint "eagle-import:LEDC2012X89N")
      (fields
        (field (name "MANUFACTURER_PART_NUMBER") "SFH 3716")
        (field (name "MOUSER_PART_NUMBER") "720-SFH3716")
        (field (name "RS_PART_NUMBER") "1115952P")
      )
      (libsource (lib "eagle-import") (part "SFH_3716"))
    )
  )
  (nets
    (net (code "1") (name "+5V") (class "Default")
      (node (ref "JP1") (pin "2") (pinfunction "2_2") (pintype "passive"))
      (node (ref "MUX1") (pin "24") (pinfunction "VCC_24") (pintype "bidirectional"))
      (node (ref "MUX2") (pin "24") (pinfunction "VCC_24") (pintype "bidirectional"))
      (node (ref "MUX3") (pin "24") (pinfunction "VCC_24") (pintype "bidirectional"))
      (node (ref "MUX4") (pin "24") (pinfunction "VCC_24") (pintype "bidirectional"))
    )
    (net (code "2") (name "/$") (class "Default")
      (node (ref "MUX2") (pin "2") (pinfunction "CHAN7_2") (pintype "bidirectional"))
    )
    (net (code "3") (name "/$1") (class "Default")
      (node (ref "MUX2") (pin "3") (pinfunction "CHAN6_3") (pintype "bidirectional"))
    )
    (net (code "4") (name "/$3") (class "Default")
      (node (ref "MUX4") (pin "17") (pinfunction "CHAN14_17") (pintype "bidirectional"))
    )
    (net (code "5") (name "/$4") (class "Default")
      (node (ref "MUX4") (pin "16") (pinfunction "CHAN15_16") (pintype "bidirectional"))
    )
    (net (code "6") (name "/+3,3V") (class "Default")
      (node (ref "JP1") (pin "11") (pinfunction "11_11") (pintype "passive"))
      (node (ref "R11") (pin "1") (pinfunction "1_1") (pintype "passive"))
      (node (ref "R14") (pin "1") (pinfunction "1_1") (pintype "passive"))
      (node (ref "R17") (pin "1") (pinfunction "1_1") (pintype "passive"))
      (node (ref "R2") (pin "1") (pinfunction "1_1") (pintype "passive"))
      (node (ref "R20") (pin "1") (pinfunction "1_1") (pintype "passive"))
      (node (ref "R23") (pin "1") (pinfunction "1_1") (pintype "passive"))
      (node (ref "R26") (pin "1") (pinfunction "1_1") (pintype "passive"))
      (node (ref "R29") (pin "1") (pinfunction "1_1") (pintype "passive"))
      (node (ref "R32") (pin "1") (pinfunction "1_1") (pintype "passive"))
      (node (ref "R35") (pin "1") (pinfunction "1_1") (pintype "passive"))
      (node (ref "R38") (pin "1") (pinfunction "1_1") (pintype "passive"))
      (node (ref "R41") (pin "1") (pinfunction "1_1") (pintype "passive"))
      (node (ref "R44") (pin "1") (pinfunction "1_1") (pintype "passive"))
      (node (ref "R47") (pin "1") (pinfunction "1_1") (pintype "passive"))
      (node (ref "R5") (pin "1") (pinfunction "1_1") (pintype "passive"))
      (node (ref "R50") (pin "1") (pinfunction "1_1") (pintype "passive"))
      (node (ref "R53") (pin "1") (pinfunction "1_1") (pintype "passive"))
      (node (ref "R56") (pin "1") (pinfunction "1_1") (pintype "passive"))
      (node (ref "R59") (pin "1") (pinfunction "1_1") (pintype "passive"))
      (node (ref "R62") (pin "1") (pinfunction "1_1") (pintype "passive"))
      (node (ref "R65") (pin "1") (pinfunction "1_1") (pintype "passive"))
      (node (ref "R68") (pin "1") (pinfunction "1_1") (pintype "passive"))
      (node (ref "R71") (pin "1") (pinfunction "1_1") (pintype "passive"))
      (node (ref "R74") (pin "1") (pinfunction "1_1") (pintype "passive"))
      (node (ref "R77") (pin "1") (pinfunction "1_1") (pintype "passive"))
      (node (ref "R8") (pin "1") (pinfunction "1_1") (pintype "passive"))
      (node (ref "R80") (pin "1") (pinfunction "1_1") (pintype "passive"))
      (node (ref "R83") (pin "1") (pinfunction "1_1") (pintype "passive"))
      (node (ref "R86") (pin "1") (pinfunction "1_1") (pintype "passive"))
      (node (ref "R89") (pin "1") (pinfunction "1_1") (pintype "passive"))
      (node (ref "R92") (pin "1") (pinfunction "1_1") (pintype "passive"))
      (node (ref "SFH1") (pin "2") (pinfunction "A_2") (pintype "bidirectional"))
      (node (ref "SFH10") (pin "2") (pinfunction "A_2") (pintype "bidirectional"))
      (node (ref "SFH11") (pin "2") (pinfunction "A_2") (pintype "bidirectional"))
      (node (ref "SFH12") (pin "2") (pinfunction "A_2") (pintype "bidirectional"))
      (node (ref "SFH13") (pin "2") (pinfunction "A_2") (pintype "bidirectional"))
      (node (ref "SFH14") (pin "2") (pinfunction "A_2") (pintype "bidirectional"))
      (node (ref "SFH15") (pin "2") (pinfunction "A_2") (pintype "bidirectional"))
      (node (ref "SFH16") (pin "2") (pinfunction "A_2") (pintype "bidirectional"))
      (node (ref "SFH17") (pin "2") (pinfunction "A_2") (pintype "bidirectional"))
      (node (ref "SFH18") (pin "2") (pinfunction "A_2") (pintype "bidirectional"))
      (node (ref "SFH19") (pin "2") (pinfunction "A_2") (pintype "bidirectional"))
      (node (ref "SFH2") (pin "2") (pinfunction "A_2") (pintype "bidirectional"))
      (node (ref "SFH20") (pin "2") (pinfunction "A_2") (pintype "bidirectional"))
      (node (ref "SFH21") (pin "2") (pinfunction "A_2") (pintype "bidirectional"))
      (node (ref "SFH22") (pin "2") (pinfunction "A_2") (pintype "bidirectional"))
      (node (ref "SFH23") (pin "2") (pinfunction "A_2") (pintype "bidirectional"))
      (node (ref "SFH24") (pin "2") (pinfunction "A_2") (pintype "bidirectional"))
      (node (ref "SFH25") (pin "2") (pinfunction "A_2") (pintype "bidirectional"))
      (node (ref "SFH26") (pin "2") (pinfunction "A_2") (pintype "bidirectional"))
      (node (ref "SFH27") (pin "2") (pinfunction "A_2") (pintype "bidirectional"))
      (node (ref "SFH28") (pin "2") (pinfunction "A_2") (pintype "bidirectional"))
      (node (ref "SFH29") (pin "2") (pinfunction "A_2") (pintype "bidirectional"))
      (node (ref "SFH3") (pin "2") (pinfunction "A_2") (pintype "bidirectional"))
      (node (ref "SFH30") (pin "2") (pinfunction "A_2") (pintype "bidirectional"))
      (node (ref "SFH31") (pin "2") (pinfunction "A_2") (pintype "bidirectional"))
      (node (ref "SFH32") (pin "2") (pinfunction "A_2") (pintype "bidirectional"))
      (node (ref "SFH33") (pin "2") (pinfunction "A_2") (pintype "bidirectional"))
      (node (ref "SFH34") (pin "2") (pinfunction "A_2") (pintype "bidirectional"))
      (node (ref "SFH35") (pin "2") (pinfunction "A_2") (pintype "bidirectional"))
      (node (ref "SFH36") (pin "2") (pinfunction "A_2") (pintype "bidirectional"))
      (node (ref "SFH37") (pin "2") (pinfunction "A_2") (pintype "bidirectional"))
      (node (ref "SFH38") (pin "2") (pinfunction "A_2") (pintype "bidirectional"))
      (node (ref "SFH39") (pin "2") (pinfunction "A_2") (pintype "bidirectional"))
      (node (ref "SFH4") (pin "2") (pinfunction "A_2") (pintype "bidirectional"))
      (node (ref "SFH40") (pin "2") (pinfunction "A_2") (pintype "bidirectional"))
      (node (ref "SFH41") (pin "2") (pinfunction "A_2") (pintype "bidirectional"))
      (node (ref "SFH42") (pin "2") (pinfunction "A_2") (pintype "bidirectional"))
      (node (ref "SFH43") (pin "2") (pinfunction "A_2") (pintype "bidirectional"))
      (node (ref "SFH44") (pin "2") (pinfunction "A_2") (pintype "bidirectional"))
      (node (ref "SFH45") (pin "2") (pinfunction "A_2") (pintype "bidirectional"))
      (node (ref "SFH46") (pin "2") (pinfunction "A_2") (pintype "bidirectional"))
      (node (ref "SFH47") (pin "2") (pinfunction "A_2") (pintype "bidirectional"))
      (node (ref "SFH48") (pin "2") (pinfunction "A_2") (pintype "bidirectional"))
      (node (ref "SFH49") (pin "2") (pinfunction "A_2") (pintype "bidirectional"))
      (node (ref "SFH5") (pin "2") (pinfunction "A_2") (pintype "bidirectional"))
      (node (ref "SFH50") (pin "2") (pinfunction "A_2") (pintype "bidirectional"))
      (node (ref "SFH51") (pin "2") (pinfunction "A_2") (pintype "bidirectional"))
      (node (ref "SFH52") (pin "2") (pinfunction "A_2") (pintype "bidirectional"))
      (node (ref "SFH53") (pin "2") (pinfunction "A_2") (pintype "bidirectional"))
      (node (ref "SFH54") (pin "2") (pinfunction "A_2") (pintype "bidirectional"))
      (node (ref "SFH55") (pin "2") (pinfunction "A_2") (pintype "bidirectional"))
      (node (ref "SFH56") (pin "2") (pinfunction "A_2") (pintype "bidirectional"))
      (node (ref "SFH57") (pin "2") (pinfunction "A_2") (pintype "bidirectional"))
      (node (ref "SFH58") (pin "2") (pinfunction "A_2") (pintype "bidirectional"))
      (node (ref "SFH59") (pin "2") (pinfunction "A_2") (pintype "bidirectional"))
      (node (ref "SFH6") (pin "2") (pinfunction "A_2") (pintype "bidirectional"))
      (node (ref "SFH60") (pin "2") (pinfunction "A_2") (pintype "bidirectional"))
      (node (ref "SFH7") (pin "2") (pinfunction "A_2") (pintype "bidirectional"))
      (node (ref "SFH8") (pin "2") (pinfunction "A_2") (pintype "bidirectional"))
      (node (ref "SFH9") (pin "2") (pinfunction "A_2") (pintype "bidirectional"))
    )
    (net (code "7") (name "/1") (class "Default")
      (node (ref "MUX1") (pin "21") (pinfunction "CHAN10_21") (pintype "bidirectional"))
      (node (ref "R1") (pin "2") (pinfunction "2_2") (pintype "passive"))
      (node (ref "SFH1") (pin "1") (pinfunction "K_1") (pintype "bidirectional"))
    )
    (net (code "8") (name "/2") (class "Default")
      (node (ref "MUX1") (pin "2") (pinfunction "CHAN7_2") (pintype "bidirectional"))
      (node (ref "R3") (pin "2") (pinfunction "2_2") (pintype "passive"))
      (node (ref "SFH2") (pin "1") (pinfunction "K_1") (pintype "bidirectional"))
    )
    (net (code "9") (name "/3") (class "Default")
      (node (ref "MUX1") (pin "9") (pinfunction "CHAN0_9") (pintype "bidirectional"))
      (node (ref "R4") (pin "2") (pinfunction "2_2") (pintype "passive"))
      (node (ref "SFH3") (pin "1") (pinfunction "K_1") (pintype "bidirectional"))
    )
    (net (code "10") (name "/4") (class "Default")
      (node (ref "MUX1") (pin "8") (pinfunction "CHAN1_8") (pintype "bidirectional"))
      (node (ref "R6") (pin "2") (pinfunction "2_2") (pintype "passive"))
      (node (ref "SFH4") (pin "1") (pinfunction "K_1") (pintype "bidirectional"))
    )
    (net (code "11") (name "/5") (class "Default")
      (node (ref "MUX1") (pin "7") (pinfunction "CHAN2_7") (pintype "bidirectional"))
      (node (ref "R7") (pin "2") (pinfunction "2_2") (pintype "passive"))
      (node (ref "SFH5") (pin "1") (pinfunction "K_1") (pintype "bidirectional"))
    )
    (net (code "12") (name "/6") (class "Default")
      (node (ref "MUX1") (pin "6") (pinfunction "CHAN3_6") (pintype "bidirectional"))
      (node (ref "R9") (pin "2") (pinfunction "2_2") (pintype "passive"))
      (node (ref "SFH6") (pin "1") (pinfunction "K_1") (pintype "bidirectional"))
    )
    (net (code "13") (name "/7") (class "Default")
      (node (ref "MUX1") (pin "5") (pinfunction "CHAN4_5") (pintype "bidirectional"))
      (node (ref "R10") (pin "2") (pinfunction "2_2") (pintype "passive"))
      (node (ref "SFH7") (pin "1") (pinfunction "K_1") (pintype "bidirectional"))
    )
    (net (code "14") (name "/8") (class "Default")
      (node (ref "MUX1") (pin "4") (pinfunction "CHAN5_4") (pintype "bidirectional"))
      (node (ref "R12") (pin "2") (pinfunction "2_2") (pintype "passive"))
      (node (ref "SFH8") (pin "1") (pinfunction "K_1") (pintype "bidirectional"))
    )
    (net (code "15") (name "/9") (class "Default")
      (node (ref "MUX1") (pin "16") (pinfunction "CHAN15_16") (pintype "bidirectional"))
      (node (ref "R13") (pin "2") (pinfunction "2_2") (pintype "passive"))
      (node (ref "SFH9") (pin "1") (pinfunction "K_1") (pintype "bidirectional"))
    )
    (net (code "16") (name "/10") (class "Default")
      (node (ref "MUX1") (pin "17") (pinfunction "CHAN14_17") (pintype "bidirectional"))
      (node (ref "R15") (pin "2") (pinfunction "2_2") (pintype "passive"))
      (node (ref "SFH10") (pin "1") (pinfunction "K_1") (pintype "bidirectional"))
    )
    (net (code "17") (name "/11") (class "Default")
      (node (ref "MUX1") (pin "18") (pinfunction "CHAN13_18") (pintype "bidirectional"))
      (node (ref "R16") (pin "2") (pinfunction "2_2") (pintype "passive"))
      (node (ref "SFH11") (pin "1") (pinfunction "K_1") (pintype "bidirectional"))
    )
    (net (code "18") (name "/12") (class "Default")
      (node (ref "MUX1") (pin "19") (pinfunction "CHAN12_19") (pintype "bidirectional"))
      (node (ref "R18") (pin "2") (pinfunction "2_2") (pintype "passive"))
      (node (ref "SFH12") (pin "1") (pinfunction "K_1") (pintype "bidirectional"))
    )
    (net (code "19") (name "/13") (class "Default")
      (node (ref "MUX1") (pin "20") (pinfunction "CHAN11_20") (pintype "bidirectional"))
      (node (ref "R19") (pin "2") (pinfunction "2_2") (pintype "passive"))
      (node (ref "SFH13") (pin "1") (pinfunction "K_1") (pintype "bidirectional"))
    )
    (net (code "20") (name "/14") (class "Default")
      (node (ref "MUX1") (pin "3") (pinfunction "CHAN6_3") (pintype "bidirectional"))
      (node (ref "R21") (pin "2") (pinfunction "2_2") (pintype "passive"))
      (node (ref "SFH14") (pin "1") (pinfunction "K_1") (pintype "bidirectional"))
    )
    (net (code "21") (name "/15") (class "Default")
      (node (ref "MUX1") (pin "22") (pinfunction "CHAN9_22") (pintype "bidirectional"))
      (node (ref "R22") (pin "2") (pinfunction "2_2") (pintype "passive"))
      (node (ref "SFH15") (pin "1") (pinfunction "K_1") (pintype "bidirectional"))
    )
    (net (code "22") (name "/16") (class "Default")
      (node (ref "MUX1") (pin "23") (pinfunction "CHAN8_23") (pintype "bidirectional"))
      (node (ref "R24") (pin "2") (pinfunction "2_2") (pintype "passive"))
      (node (ref "SFH16") (pin "1") (pinfunction "K_1") (pintype "bidirectional"))
    )
    (net (code "23") (name "/17") (class "Default")
      (node (ref "MUX4") (pin "9") (pinfunction "CHAN0_9") (pintype "bidirectional"))
      (node (ref "R25") (pin "2") (pinfunction "2_2") (pintype "passive"))
      (node (ref "SFH17") (pin "1") (pinfunction "K_1") (pintype "bidirectional"))
    )
    (net (code "24") (name "/18") (class "Default")
      (node (ref "MUX4") (pin "8") (pinfunction "CHAN1_8") (pintype "bidirectional"))
      (node (ref "R27") (pin "2") (pinfunction "2_2") (pintype "passive"))
      (node (ref "SFH18") (pin "1") (pinfunction "K_1") (pintype "bidirectional"))
    )
    (net (code "25") (name "/19") (class "Default")
      (node (ref "MUX2") (pin "16") (pinfunction "CHAN15_16") (pintype "bidirectional"))
      (node (ref "R28") (pin "2") (pinfunction "2_2") (pintype "passive"))
      (node (ref "SFH19") (pin "1") (pinfunction "K_1") (pintype "bidirectional"))
    )
    (net (code "26") (name "/20") (class "Default")
      (node (ref "MUX2") (pin "17") (pinfunction "CHAN14_17") (pintype "bidirectional"))
      (node (ref "R30") (pin "2") (pinfunction "2_2") (pintype "passive"))
      (node (ref "SFH20") (pin "1") (pinfunction "K_1") (pintype "bidirectional"))
    )
    (net (code "27") (name "/21") (class "Default")
      (node (ref "MUX2") (pin "18") (pinfunction "CHAN13_18") (pintype "bidirectional"))
      (node (ref "R31") (pin "2") (pinfunction "2_2") (pintype "passive"))
      (node (ref "SFH21") (pin "1") (pinfunction "K_1") (pintype "bidirectional"))
    )
    (net (code "28") (name "/22") (class "Default")
      (node (ref "MUX2") (pin "19") (pinfunction "CHAN12_19") (pintype "bidirectional"))
      (node (ref "R33") (pin "2") (pinfunction "2_2") (pintype "passive"))
      (node (ref "SFH22") (pin "1") (pinfunction "K_1") (pintype "bidirectional"))
    )
    (net (code "29") (name "/23") (class "Default")
      (node (ref "MUX2") (pin "20") (pinfunction "CHAN11_20") (pintype "bidirectional"))
      (node (ref "R34") (pin "2") (pinfunction "2_2") (pintype "passive"))
      (node (ref "SFH23") (pin "1") (pinfunction "K_1") (pintype "bidirectional"))
    )
    (net (code "30") (name "/24") (class "Default")
      (node (ref "MUX2") (pin "21") (pinfunction "CHAN10_21") (pintype "bidirectional"))
      (node (ref "R36") (pin "2") (pinfunction "2_2") (pintype "passive"))
      (node (ref "SFH24") (pin "1") (pinfunction "K_1") (pintype "bidirectional"))
    )
    (net (code "31") (name "/25") (class "Default")
      (node (ref "MUX2") (pin "22") (pinfunction "CHAN9_22") (pintype "bidirectional"))
      (node (ref "R37") (pin "2") (pinfunction "2_2") (pintype "passive"))
      (node (ref "SFH25") (pin "1") (pinfunction "K_1") (pintype "bidirectional"))
    )
    (net (code "32") (name "/26") (class "Default")
      (node (ref "MUX2") (pin "23") (pinfunction "CHAN8_23") (pintype "bidirectional"))
      (node (ref "R39") (pin "2") (pinfunction "2_2") (pintype "passive"))
      (node (ref "SFH26") (pin "1") (pinfunction "K_1") (pintype "bidirectional"))
    )
    (net (code "33") (name "/27") (class "Default")
      (node (ref "MUX2") (pin "9") (pinfunction "CHAN0_9") (pintype "bidirectional"))
      (node (ref "R40") (pin "2") (pinfunction "2_2") (pintype "passive"))
      (node (ref "SFH27") (pin "1") (pinfunction "K_1") (pintype "bidirectional"))
    )
    (net (code "34") (name "/28") (class "Default")
      (node (ref "MUX2") (pin "8") (pinfunction "CHAN1_8") (pintype "bidirectional"))
      (node (ref "R42") (pin "2") (pinfunction "2_2") (pintype "passive"))
      (node (ref "SFH28") (pin "1") (pinfunction "K_1") (pintype "bidirectional"))
    )
    (net (code "35") (name "/29") (class "Default")
      (node (ref "MUX2") (pin "7") (pinfunction "CHAN2_7") (pintype "bidirectional"))
      (node (ref "R43") (pin "2") (pinfunction "2_2") (pintype "passive"))
      (node (ref "SFH29") (pin "1") (pinfunction "K_1") (pintype "bidirectional"))
    )
    (net (code "36") (name "/30") (class "Default")
      (node (ref "MUX2") (pin "6") (pinfunction "CHAN3_6") (pintype "bidirectional"))
      (node (ref "R45") (pin "2") (pinfunction "2_2") (pintype "passive"))
      (node (ref "SFH30") (pin "1") (pinfunction "K_1") (pintype "bidirectional"))
    )
    (net (code "37") (name "/31") (class "Default")
      (node (ref "MUX2") (pin "5") (pinfunction "CHAN4_5") (pintype "bidirectional"))
      (node (ref "R46") (pin "2") (pinfunction "2_2") (pintype "passive"))
      (node (ref "SFH31") (pin "1") (pinfunction "K_1") (pintype "bidirectional"))
    )
    (net (code "38") (name "/32") (class "Default")
      (node (ref "MUX2") (pin "4") (pinfunction "CHAN5_4") (pintype "bidirectional"))
      (node (ref "R48") (pin "2") (pinfunction "2_2") (pintype "passive"))
      (node (ref "SFH32") (pin "1") (pinfunction "K_1") (pintype "bidirectional"))
    )
    (net (code "39") (name "/33") (class "Default")
      (node (ref "MUX3") (pin "16") (pinfunction "CHAN15_16") (pintype "bidirectional"))
      (node (ref "R49") (pin "2") (pinfunction "2_2") (pintype "passive"))
      (node (ref "SFH33") (pin "1") (pinfunction "K_1") (pintype "bidirectional"))
    )
    (net (code "40") (name "/34") (class "Default")
      (node (ref "MUX3") (pin "17") (pinfunction "CHAN14_17") (pintype "bidirectional"))
      (node (ref "R51") (pin "2") (pinfunction "2_2") (pintype "passive"))
      (node (ref "SFH34") (pin "1") (pinfunction "K_1") (pintype "bidirectional"))
    )
    (net (code "41") (name "/35") (class "Default")
      (node (ref "MUX3") (pin "18") (pinfunction "CHAN13_18") (pintype "bidirectional"))
      (node (ref "R52") (pin "2") (pinfunction "2_2") (pintype "passive"))
      (node (ref "SFH35") (pin "1") (pinfunction "K_1") (pintype "bidirectional"))
    )
    (net (code "42") (name "/36") (class "Default")
      (node (ref "MUX3") (pin "19") (pinfunction "CHAN12_19") (pintype "bidirectional"))
      (node (ref "R54") (pin "2") (pinfunction "2_2") (pintype "passive"))
      (node (ref "SFH36") (pin "1") (pinfunction "K_1") (pintype "bidirectional"))
    )
    (net (code "43") (name "/37") (class "Default")
      (node (ref "MUX3") (pin "20") (pinfunction "CHAN11_20") (pintype "bidirectional"))
      (node (ref "R55") (pin "2") (pinfunction "2_2") (pintype "passive"))
      (node (ref "SFH37") (pin "1") (pinfunction "K_1") (pintype "bidirectional"))
    )
    (net (code "44") (name "/38") (class "Default")
      (node (ref "MUX3") (pin "21") (pinfunction "CHAN10_21") (pintype "bidirectional"))
      (node (ref "R57") (pin "2") (pinfunction "2_2") (pintype "passive"))
      (node (ref "SFH38") (pin "1") (pinfunction "K_1") (pintype "bidirectional"))
    )
    (net (code "45") (name "/39") (class "Default")
      (node (ref "MUX3") (pin "22") (pinfunction "CHAN9_22") (pintype "bidirectional"))
      (node (ref "R58") (pin "2") (pinfunction "2_2") (pintype "passive"))
      (node (ref "SFH39") (pin "1") (pinfunction "K_1") (pintype "bidirectional"))
    )
    (net (code "46") (name "/40") (class "Default")
      (node (ref "MUX3") (pin "23") (pinfunction "CHAN8_23") (pintype "bidirectional"))
      (node (ref "R60") (pin "2") (pinfunction "2_2") (pintype "passive"))
      (node (ref "SFH40") (pin "1") (pinfunction "K_1") (pintype "bidirectional"))
    )
    (net (code "47") (name "/41") (class "Default")
      (node (ref "MUX3") (pin "9") (pinfunction "CHAN0_9") (pintype "bidirectional"))
      (node (ref "R61") (pin "2") (pinfunction "2_2") (pintype "passive"))
      (node (ref "SFH41") (pin "1") (pinfunction "K_1") (pintype "bidirectional"))
    )
    (net (code "48") (name "/42") (class "Default")
      (node (ref "MUX3") (pin "8") (pinfunction "CHAN1_8") (pintype "bidirectional"))
      (node (ref "R63") (pin "2") (pinfunction "2_2") (pintype "passive"))
      (node (ref "SFH42") (pin "1") (pinfunction "K_1") (pintype "bidirectional"))
    )
    (net (code "49") (name "/43") (class "Default")
      (node (ref "MUX3") (pin "7") (pinfunction "CHAN2_7") (pintype "bidirectional"))
      (node (ref "R64") (pin "2") (pinfunction "2_2") (pintype "passive"))
      (node (ref "SFH43") (pin "1") (pinfunction "K_1") (pintype "bidirectional"))
    )
    (net (code "50") (name "/44") (class "Default")
      (node (ref "MUX3") (pin "6") (pinfunction "CHAN3_6") (pintype "bidirectional"))
      (node (ref "R66") (pin "2") (pinfunction "2_2") (pintype "passive"))
      (node (ref "SFH44") (pin "1") (pinfunction "K_1") (pintype "bidirectional"))
    )
    (net (code "51") (name "/45") (class "Default")
      (node (ref "MUX3") (pin "5") (pinfunction "CHAN4_5") (pintype "bidirectional"))
      (node (ref "R67") (pin "2") (pinfunction "2_2") (pintype "passive"))
      (node (ref "SFH45") (pin "1") (pinfunction "K_1") (pintype "bidirectional"))
    )
    (net (code "52") (name "/46") (class "Default")
      (node (ref "MUX3") (pin "4") (pinfunction "CHAN5_4") (pintype "bidirectional"))
      (node (ref "R69") (pin "2") (pinfunction "2_2") (pintype "passive"))
      (node (ref "SFH46") (pin "1") (pinfunction "K_1") (pintype "bidirectional"))
    )
    (net (code "53") (name "/47") (class "Default")
      (node (ref "MUX3") (pin "3") (pinfunction "CHAN6_3") (pintype "bidirectional"))
      (node (ref "R70") (pin "2") (pinfunction "2_2") (pintype "passive"))
      (node (ref "SFH47") (pin "1") (pinfunction "K_1") (pintype "bidirectional"))
    )
    (net (code "54") (name "/48") (class "Default")
      (node (ref "MUX3") (pin "2") (pinfunction "CHAN7_2") (pintype "bidirectional"))
      (node (ref "R72") (pin "2") (pinfunction "2_2") (pintype "passive"))
      (node (ref "SFH48") (pin "1") (pinfunction "K_1") (pintype "bidirectional"))
    )
    (net (code "55") (name "/49") (class "Default")
      (node (ref "MUX4") (pin "19") (pinfunction "CHAN12_19") (pintype "bidirectional"))
      (node (ref "R73") (pin "2") (pinfunction "2_2") (pintype "passive"))
      (node (ref "SFH49") (pin "1") (pinfunction "K_1") (pintype "bidirectional"))
    )
    (net (code "56") (name "/50") (class "Default")
      (node (ref "MUX4") (pin "23") (pinfunction "CHAN8_23") (pintype "bidirectional"))
      (node (ref "R75") (pin "2") (pinfunction "2_2") (pintype "passive"))
      (node (ref "SFH50") (pin "1") (pinfunction "K_1") (pintype "bidirectional"))
    )
    (net (code "57") (name "/51") (class "Default")
      (node (ref "MUX4") (pin "2") (pinfunction "CHAN7_2") (pintype "bidirectional"))
      (node (ref "R76") (pin "2") (pinfunction "2_2") (pintype "passive"))
      (node (ref "SFH51") (pin "1") (pinfunction "K_1") (pintype "bidirectional"))
    )
    (net (code "58") (name "/52") (class "Default")
      (node (ref "MUX4") (pin "3") (pinfunction "CHAN6_3") (pintype "bidirectional"))
      (node (ref "R78") (pin "2") (pinfunction "2_2") (pintype "passive"))
      (node (ref "SFH52") (pin "1") (pinfunction "K_1") (pintype "bidirectional"))
    )
    (net (code "59") (name "/53") (class "Default")
      (node (ref "MUX4") (pin "4") (pinfunction "CHAN5_4") (pintype "bidirectional"))
      (node (ref "R79") (pin "2") (pinfunction "2_2") (pintype "passive"))
      (node (ref "SFH53") (pin "1") (pinfunction "K_1") (pintype "bidirectional"))
    )
    (net (code "60") (name "/54") (class "Default")
      (node (ref "MUX4") (pin "5") (pinfunction "CHAN4_5") (pintype "bidirectional"))
      (node (ref "R81") (pin "2") (pinfunction "2_2") (pintype "passive"))
      (node (ref "SFH54") (pin "1") (pinfunction "K_1") (pintype "bidirectional"))
    )
    (net (code "61") (name "/55") (class "Default")
      (node (ref "MUX4") (pin "6") (pinfunction "CHAN3_6") (pintype "bidirectional"))
      (node (ref "R82") (pin "2") (pinfunction "2_2") (pintype "passive"))
      (node (ref "SFH55") (pin "1") (pinfunction "K_1") (pintype "bidirectional"))
    )
    (net (code "62") (name "/56") (class "Default")
      (node (ref "MUX4") (pin "7") (pinfunction "CHAN2_7") (pintype "bidirectional"))
      (node (ref "R84") (pin "2") (pinfunction "2_2") (pintype "passive"))
      (node (ref "SFH56") (pin "1") (pinfunction "K_1") (pintype "bidirectional"))
    )
    (net (code "63") (name "/57") (class "Default")
      (node (ref "MUX4") (pin "18") (pinfunction "CHAN13_18") (pintype "bidirectional"))
      (node (ref "R85") (pin "2") (pinfunction "2_2") (pintype "passive"))
      (node (ref "SFH57") (pin "1") (pinfunction "K_1") (pintype "bidirectional"))
    )
    (net (code "64") (name "/58") (class "Default")
      (node (ref "MUX4") (pin "22") (pinfunction "CHAN9_22") (pintype "bidirectional"))
      (node (ref "R87") (pin "2") (pinfunction "2_2") (pintype "passive"))
      (node (ref "SFH58") (pin "1") (pinfunction "K_1") (pintype "bidirectional"))
    )
    (net (code "65") (name "/59") (class "Default")
      (node (ref "MUX4") (pin "21") (pinfunction "CHAN10_21") (pintype "bidirectional"))
      (node (ref "R88") (pin "2") (pinfunction "2_2") (pintype "passive"))
      (node (ref "SFH59") (pin "1") (pinfunction "K_1") (pintype "bidirectional"))
    )
    (net (code "66") (name "/60") (class "Default")
      (node (ref "MUX4") (pin "20") (pinfunction "CHAN11_20") (pintype "bidirectional"))
      (node (ref "R90") (pin "2") (pinfunction "2_2") (pintype "passive"))
      (node (ref "SFH60") (pin "1") (pinfunction "K_1") (pintype "bidirectional"))
    )
    (net (code "67") (name "/S0") (class "Default")
      (node (ref "JP1") (pin "4") (pinfunction "4_4") (pintype "passive"))
      (node (ref "MUX1") (pin "10") (pinfunction "S0_10") (pintype "input"))
      (node (ref "MUX2") (pin "10") (pinfunction "S0_10") (pintype "input"))
      (node (ref "MUX3") (pin "10") (pinfunction "S0_10") (pintype "input"))
      (node (ref "MUX4") (pin "10") (pinfunction "S0_10") (pintype "input"))
    )
    (net (code "68") (name "/S1") (class "Default")
      (node (ref "JP1") (pin "6") (pinfunction "6_6") (pintype "passive"))
      (node (ref "MUX1") (pin "11") (pinfunction "S1_11") (pintype "input"))
      (node (ref "MUX2") (pin "11") (pinfunction "S1_11") (pintype "input"))
      (node (ref "MUX3") (pin "11") (pinfunction "S1_11") (pintype "input"))
      (node (ref "MUX4") (pin "11") (pinfunction "S1_11") (pintype "input"))
    )
    (net (code "69") (name "/S2") (class "Default")
      (node (ref "JP1") (pin "8") (pinfunction "8_8") (pintype "passive"))
      (node (ref "MUX1") (pin "14") (pinfunction "S2_14") (pintype "input"))
      (node (ref "MUX2") (pin "14") (pinfunction "S2_14") (pintype "input"))
      (node (ref "MUX3") (pin "14") (pinfunction "S2_14") (pintype "input"))
      (node (ref "MUX4") (pin "14") (pinfunction "S2_14") (pintype "input"))
    )
    (net (code "70") (name "/S3") (class "Default")
      (node (ref "JP1") (pin "10") (pinfunction "10_10") (pintype "passive"))
      (node (ref "MUX1") (pin "13") (pinfunction "S3_13") (pintype "input"))
      (node (ref "MUX2") (pin "13") (pinfunction "S3_13") (pintype "input"))
      (node (ref "MUX3") (pin "13") (pinfunction "S3_13") (pintype "input"))
      (node (ref "MUX4") (pin "13") (pinfunction "S3_13") (pintype "input"))
    )
    (net (code "71") (name "/SIGNAL_OUT_0") (class "Default")
      (node (ref "JP1") (pin "1") (pinfunction "1_1") (pintype "passive"))
      (node (ref "MUX1") (pin "1") (pinfunction "COM_1") (pintype "bidirectional"))
    )
    (net (code "72") (name "/SIGNAL_OUT_1") (class "Default")
      (node (ref "JP1") (pin "3") (pinfunction "3_3") (pintype "passive"))
      (node (ref "MUX2") (pin "1") (pinfunction "COM_1") (pintype "bidirectional"))
    )
    (net (code "73") (name "/SIGNAL_OUT_2") (class "Default")
      (node (ref "JP1") (pin "5") (pinfunction "5_5") (pintype "passive"))
      (node (ref "MUX3") (pin "1") (pinfunction "COM_1") (pintype "bidirectional"))
    )
    (net (code "74") (name "/SIGNAL_OUT_3") (class "Default")
      (node (ref "JP1") (pin "7") (pinfunction "7_7") (pintype "passive"))
      (node (ref "MUX4") (pin "1") (pinfunction "COM_1") (pintype "bidirectional"))
    )
    (net (code "75") (name "GND") (class "Default")
      (node (ref "JP1") (pin "9") (pinfunction "9_9") (pintype "passive"))
      (node (ref "LED_1") (pin "123") (pinfunction "GND_123") (pintype "bidirectional"))
      (node (ref "LED_10") (pin "123") (pinfunction "GND_123") (pintype "bidirectional"))
      (node (ref "LED_11") (pin "123") (pinfunction "GND_123") (pintype "bidirectional"))
      (node (ref "LED_12") (pin "123") (pinfunction "GND_123") (pintype "bidirectional"))
      (node (ref "LED_13") (pin "123") (pinfunction "GND_123") (pintype "bidirectional"))
      (node (ref "LED_14") (pin "123") (pinfunction "GND_123") (pintype "bidirectional"))
      (node (ref "LED_15") (pin "123") (pinfunction "GND_123") (pintype "bidirectional"))
      (node (ref "LED_16") (pin "123") (pinfunction "GND_123") (pintype "bidirectional"))
      (node (ref "LED_17") (pin "123") (pinfunction "GND_123") (pintype "bidirectional"))
      (node (ref "LED_18") (pin "123") (pinfunction "GND_123") (pintype "bidirectional"))
      (node (ref "LED_19") (pin "123") (pinfunction "GND_123") (pintype "bidirectional"))
      (node (ref "LED_2") (pin "123") (pinfunction "GND_123") (pintype "bidirectional"))
      (node (ref "LED_20") (pin "123") (pinfunction "GND_123") (pintype "bidirectional"))
      (node (ref "LED_21") (pin "123") (pinfunction "GND_123") (pintype "bidirectional"))
      (node (ref "LED_22") (pin "123") (pinfunction "GND_123") (pintype "bidirectional"))
      (node (ref "LED_23") (pin "123") (pinfunction "GND_123") (pintype "bidirectional"))
      (node (ref "LED_24") (pin "123") (pinfunction "GND_123") (pintype "bidirectional"))
      (node (ref "LED_25") (pin "123") (pinfunction "GND_123") (pintype "bidirectional"))
      (node (ref "LED_26") (pin "123") (pinfunction "GND_123") (pintype "bidirectional"))
      (node (ref "LED_27") (pin "123") (pinfunction "GND_123") (pintype "bidirectional"))
      (node (ref "LED_28") (pin "123") (pinfunction "GND_123") (pintype "bidirectional"))
      (node (ref "LED_29") (pin "123") (pinfunction "GND_123") (pintype "bidirectional"))
      (node (ref "LED_3") (pin "123") (pinfunction "GND_123") (pintype "bidirectional"))
      (node (ref "LED_30") (pin "123") (pinfunction "GND_123") (pintype "bidirectional"))
      (node (ref "LED_31") (pin "123") (pinfunction "GND_123") (pintype "bidirectional"))
      (node (ref "LED_4") (pin "123") (pinfunction "GND_123") (pintype "bidirectional"))
      (node (ref "LED_5") (pin "123") (pinfunction "GND_123") (pintype "bidirectional"))
      (node (ref "LED_6") (pin "123") (pinfunction "GND_123") (pintype "bidirectional"))
      (node (ref "LED_7") (pin "123") (pinfunction "GND_123") (pintype "bidirectional"))
      (node (ref "LED_8") (pin "123") (pinfunction "GND_123") (pintype "bidirectional"))
      (node (ref "LED_9") (pin "123") (pinfunction "GND_123") (pintype "bidirectional"))
      (node (ref "MUX1") (pin "12") (pinfunction "GND_12") (pintype "bidirectional"))
      (node (ref "MUX1") (pin "15") (pinfunction "EN_15") (pintype "input"))
      (node (ref "MUX2") (pin "12") (pinfunction "GND_12") (pintype "bidirectional"))
      (node (ref "MUX2") (pin "15") (pinfunction "EN_15") (pintype "input"))
      (node (ref "MUX3") (pin "12") (pinfunction "GND_12") (pintype "bidirectional"))
      (node (ref "MUX3") (pin "15") (pinfunction "EN_15") (pintype "input"))
      (node (ref "MUX4") (pin "12") (pinfunction "GND_12") (pintype "bidirectional"))
      (node (ref "MUX4") (pin "15") (pinfunction "EN_15") (pintype "input"))
      (node (ref "R1") (pin "1") (pinfunction "1_1") (pintype "passive"))
      (node (ref "R10") (pin "1") (pinfunction "1_1") (pintype "passive"))
      (node (ref "R12") (pin "1") (pinfunction "1_1") (pintype "passive"))
      (node (ref "R13") (pin "1") (pinfunction "1_1") (pintype "passive"))
      (node (ref "R15") (pin "1") (pinfunction "1_1") (pintype "passive"))
      (node (ref "R16") (pin "1") (pinfunction "1_1") (pintype "passive"))
      (node (ref "R18") (pin "1") (pinfunction "1_1") (pintype "passive"))
      (node (ref "R19") (pin "1") (pinfunction "1_1") (pintype "passive"))
      (node (ref "R21") (pin "1") (pinfunction "1_1") (pintype "passive"))
      (node (ref "R22") (pin "1") (pinfunction "1_1") (pintype "passive"))
      (node (ref "R24") (pin "1") (pinfunction "1_1") (pintype "passive"))
      (node (ref "R25") (pin "1") (pinfunction "1_1") (pintype "passive"))
      (node (ref "R27") (pin "1") (pinfunction "1_1") (pintype "passive"))
      (node (ref "R28") (pin "1") (pinfunction "1_1") (pintype "passive"))
      (node (ref "R3") (pin "1") (pinfunction "1_1") (pintype "passive"))
      (node (ref "R30") (pin "1") (pinfunction "1_1") (pintype "passive"))
      (node (ref "R31") (pin "1") (pinfunction "1_1") (pintype "passive"))
      (node (ref "R33") (pin "1") (pinfunction "1_1") (pintype "passive"))
      (node (ref "R34") (pin "1") (pinfunction "1_1") (pintype "passive"))
      (node (ref "R36") (pin "1") (pinfunction "1_1") (pintype "passive"))
      (node (ref "R37") (pin "1") (pinfunction "1_1") (pintype "passive"))
      (node (ref "R39") (pin "1") (pinfunction "1_1") (pintype "passive"))
      (node (ref "R4") (pin "1") (pinfunction "1_1") (pintype "passive"))
      (node (ref "R40") (pin "1") (pinfunction "1_1") (pintype "passive"))
      (node (ref "R42") (pin "1") (pinfunction "1_1") (pintype "passive"))
      (node (ref "R43") (pin "1") (pinfunction "1_1") (pintype "passive"))
      (node (ref "R45") (pin "1") (pinfunction "1_1") (pintype "passive"))
      (node (ref "R46") (pin "1") (pinfunction "1_1") (pintype "passive"))
      (node (ref "R48") (pin "1") (pinfunction "1_1") (pintype "passive"))
      (node (ref "R49") (pin "1") (pinfunction "1_1") (pintype "passive"))
      (node (ref "R51") (pin "1") (pinfunction "1_1") (pintype "passive"))
      (node (ref "R52") (pin "1") (pinfunction "1_1") (pintype "passive"))
      (node (ref "R54") (pin "1") (pinfunction "1_1") (pintype "passive"))
      (node (ref "R55") (pin "1") (pinfunction "1_1") (pintype "passive"))
      (node (ref "R57") (pin "1") (pinfunction "1_1") (pintype "passive"))
      (node (ref "R58") (pin "1") (pinfunction "1_1") (pintype "passive"))
      (node (ref "R6") (pin "1") (pinfunction "1_1") (pintype "passive"))
      (node (ref "R60") (pin "1") (pinfunction "1_1") (pintype "passive"))
      (node (ref "R61") (pin "1") (pinfunction "1_1") (pintype "passive"))
      (node (ref "R63") (pin "1") (pinfunction "1_1") (pintype "passive"))
      (node (ref "R64") (pin "1") (pinfunction "1_1") (pintype "passive"))
      (node (ref "R66") (pin "1") (pinfunction "1_1") (pintype "passive"))
      (node (ref "R67") (pin "1") (pinfunction "1_1") (pintype "passive"))
      (node (ref "R69") (pin "1") (pinfunction "1_1") (pintype "passive"))
      (node (ref "R7") (pin "1") (pinfunction "1_1") (pintype "passive"))
      (node (ref "R70") (pin "1") (pinfunction "1_1") (pintype "passive"))
      (node (ref "R72") (pin "1") (pinfunction "1_1") (pintype "passive"))
      (node (ref "R73") (pin "1") (pinfunction "1_1") (pintype "passive"))
      (node (ref "R75") (pin "1") (pinfunction "1_1") (pintype "passive"))
      (node (ref "R76") (pin "1") (pinfunction "1_1") (pintype "passive"))
      (node (ref "R78") (pin "1") (pinfunction "1_1") (pintype "passive"))
      (node (ref "R79") (pin "1") (pinfunction "1_1") (pintype "passive"))
      (node (ref "R81") (pin "1") (pinfunction "1_1") (pintype "passive"))
      (node (ref "R82") (pin "1") (pinfunction "1_1") (pintype "passive"))
      (node (ref "R84") (pin "1") (pinfunction "1_1") (pintype "passive"))
      (node (ref "R85") (pin "1") (pinfunction "1_1") (pintype "passive"))
      (node (ref "R87") (pin "1") (pinfunction "1_1") (pintype "passive"))
      (node (ref "R88") (pin "1") (pinfunction "1_1") (pintype "passive"))
      (node (ref "R9") (pin "1") (pinfunction "1_1") (pintype "passive"))
      (node (ref "R90") (pin "1") (pinfunction "1_1") (pintype "passive"))
    )
    (net (code "76") (name "Net-(LED_1-+3V3)") (class "Default")
      (node (ref "LED_1") (pin "456") (pinfunction "+3V3_456") (pintype "bidirectional"))
      (node (ref "R2") (pin "2") (pinfunction "2_2") (pintype "passive"))
    )
    (net (code "77") (name "Net-(LED_2-+3V3)") (class "Default")
      (node (ref "LED_2") (pin "456") (pinfunction "+3V3_456") (pintype "bidirectional"))
      (node (ref "R5") (pin "2") (pinfunction "2_2") (pintype "passive"))
    )
    (net (code "78") (name "Net-(LED_3-+3V3)") (class "Default")
      (node (ref "LED_3") (pin "456") (pinfunction "+3V3_456") (pintype "bidirectional"))
      (node (ref "R8") (pin "2") (pinfunction "2_2") (pintype "passive"))
    )
    (net (code "79") (name "Net-(LED_4-+3V3)") (class "Default")
      (node (ref "LED_4") (pin "456") (pinfunction "+3V3_456") (pintype "bidirectional"))
      (node (ref "R11") (pin "2") (pinfunction "2_2") (pintype "passive"))
    )
    (net (code "80") (name "Net-(LED_5-+3V3)") (class "Default")
      (node (ref "LED_5") (pin "456") (pinfunction "+3V3_456") (pintype "bidirectional"))
      (node (ref "R14") (pin "2") (pinfunction "2_2") (pintype "passive"))
    )
    (net (code "81") (name "Net-(LED_6-+3V3)") (class "Default")
      (node (ref "LED_6") (pin "456") (pinfunction "+3V3_456") (pintype "bidirectional"))
      (node (ref "R17") (pin "2") (pinfunction "2_2") (pintype "passive"))
    )
    (net (code "82") (name "Net-(LED_7-+3V3)") (class "Default")
      (node (ref "LED_7") (pin "456") (pinfunction "+3V3_456") (pintype "bidirectional"))
      (node (ref "R20") (pin "2") (pinfunction "2_2") (pintype "passive"))
    )
    (net (code "83") (name "Net-(LED_8-+3V3)") (class "Default")
      (node (ref "LED_8") (pin "456") (pinfunction "+3V3_456") (pintype "bidirectional"))
      (node (ref "R23") (pin "2") (pinfunction "2_2") (pintype "passive"))
    )
    (net (code "84") (name "Net-(LED_9-+3V3)") (class "Default")
      (node (ref "LED_9") (pin "456") (pinfunction "+3V3_456") (pintype "bidirectional"))
      (node (ref "R26") (pin "2") (pinfunction "2_2") (pintype "passive"))
    )
    (net (code "85") (name "Net-(LED_10-+3V3)") (class "Default")
      (node (ref "LED_10") (pin "456") (pinfunction "+3V3_456") (pintype "bidirectional"))
      (node (ref "R29") (pin "2") (pinfunction "2_2") (pintype "passive"))
    )
    (net (code "86") (name "Net-(LED_11-+3V3)") (class "Default")
      (node (ref "LED_11") (pin "456") (pinfunction "+3V3_456") (pintype "bidirectional"))
      (node (ref "R32") (pin "2") (pinfunction "2_2") (pintype "passive"))
    )
    (net (code "87") (name "Net-(LED_12-+3V3)") (class "Default")
      (node (ref "LED_12") (pin "456") (pinfunction "+3V3_456") (pintype "bidirectional"))
      (node (ref "R35") (pin "2") (pinfunction "2_2") (pintype "passive"))
    )
    (net (code "88") (name "Net-(LED_13-+3V3)") (class "Default")
      (node (ref "LED_13") (pin "456") (pinfunction "+3V3_456") (pintype "bidirectional"))
      (node (ref "R38") (pin "2") (pinfunction "2_2") (pintype "passive"))
    )
    (net (code "89") (name "Net-(LED_14-+3V3)") (class "Default")
      (node (ref "LED_14") (pin "456") (pinfunction "+3V3_456") (pintype "bidirectional"))
      (node (ref "R41") (pin "2") (pinfunction "2_2") (pintype "passive"))
    )
    (net (code "90") (name "Net-(LED_15-+3V3)") (class "Default")
      (node (ref "LED_15") (pin "456") (pinfunction "+3V3_456") (pintype "bidirectional"))
      (node (ref "R44") (pin "2") (pinfunction "2_2") (pintype "passive"))
    )
    (net (code "91") (name "Net-(LED_16-+3V3)") (class "Default")
      (node (ref "LED_16") (pin "456") (pinfunction "+3V3_456") (pintype "bidirectional"))
      (node (ref "R47") (pin "2") (pinfunction "2_2") (pintype "passive"))
    )
    (net (code "92") (name "Net-(LED_17-+3V3)") (class "Default")
      (node (ref "LED_17") (pin "456") (pinfunction "+3V3_456") (pintype "bidirectional"))
      (node (ref "R50") (pin "2") (pinfunction "2_2") (pintype "passive"))
    )
    (net (code "93") (name "Net-(LED_18-+3V3)") (class "Default")
      (node (ref "LED_18") (pin "456") (pinfunction "+3V3_456") (pintype "bidirectional"))
      (node (ref "R53") (pin "2") (pinfunction "2_2") (pintype "passive"))
    )
    (net (code "94") (name "Net-(LED_19-+3V3)") (class "Default")
      (node (ref "LED_19") (pin "456") (pinfunction "+3V3_456") (pintype "bidirectional"))
      (node (ref "R56") (pin "2") (pinfunction "2_2") (pintype "passive"))
    )
    (net (code "95") (name "Net-(LED_20-+3V3)") (class "Default")
      (node (ref "LED_20") (pin "456") (pinfunction "+3V3_456") (pintype "bidirectional"))
      (node (ref "R59") (pin "2") (pinfunction "2_2") (pintype "passive"))
    )
    (net (code "96") (name "Net-(LED_21-+3V3)") (class "Default")
      (node (ref "LED_21") (pin "456") (pinfunction "+3V3_456") (pintype "bidirectional"))
      (node (ref "R62") (pin "2") (pinfunction "2_2") (pintype "passive"))
    )
    (net (code "97") (name "Net-(LED_22-+3V3)") (class "Default")
      (node (ref "LED_22") (pin "456") (pinfunction "+3V3_456") (pintype "bidirectional"))
      (node (ref "R65") (pin "2") (pinfunction "2_2") (pintype "passive"))
    )
    (net (code "98") (name "Net-(LED_23-+3V3)") (class "Default")
      (node (ref "LED_23") (pin "456") (pinfunction "+3V3_456") (pintype "bidirectional"))
      (node (ref "R68") (pin "2") (pinfunction "2_2") (pintype "passive"))
    )
    (net (code "99") (name "Net-(LED_24-+3V3)") (class "Default")
      (node (ref "LED_24") (pin "456") (pinfunction "+3V3_456") (pintype "bidirectional"))
      (node (ref "R71") (pin "2") (pinfunction "2_2") (pintype "passive"))
    )
    (net (code "100") (name "Net-(LED_25-+3V3)") (class "Default")
      (node (ref "LED_25") (pin "456") (pinfunction "+3V3_456") (pintype "bidirectional"))
      (node (ref "R74") (pin "2") (pinfunction "2_2") (pintype "passive"))
    )
    (net (code "101") (name "Net-(LED_26-+3V3)") (class "Default")
      (node (ref "LED_26") (pin "456") (pinfunction "+3V3_456") (pintype "bidirectional"))
      (node (ref "R77") (pin "2") (pinfunction "2_2") (pintype "passive"))
    )
    (net (code "102") (name "Net-(LED_27-+3V3)") (class "Default")
      (node (ref "LED_27") (pin "456") (pinfunction "+3V3_456") (pintype "bidirectional"))
      (node (ref "R80") (pin "2") (pinfunction "2_2") (pintype "passive"))
    )
    (net (code "103") (name "Net-(LED_28-+3V3)") (class "Default")
      (node (ref "LED_28") (pin "456") (pinfunction "+3V3_456") (pintype "bidirectional"))
      (node (ref "R83") (pin "2") (pinfunction "2_2") (pintype "passive"))
    )
    (net (code "104") (name "Net-(LED_29-+3V3)") (class "Default")
      (node (ref "LED_29") (pin "456") (pinfunction "+3V3_456") (pintype "bidirectional"))
      (node (ref "R86") (pin "2") (pinfunction "2_2") (pintype "passive"))
    )
    (net (code "105") (name "Net-(LED_30-+3V3)") (class "Default")
      (node (ref "LED_30") (pin "456") (pinfunction "+3V3_456") (pintype "bidirectional"))
      (node (ref "R89") (pin "2") (pinfunction "2_2") (pintype "passive"))
    )
    (net (code "106") (name "Net-(LED_31-+3V3)") (class "Default")
      (node (ref "LED_31") (pin "456") (pinfunction "+3V3_456") (pintype "bidirectional"))
      (node (ref "R92") (pin "2") (pinfunction "2_2") (pintype "passive"))
    )
    (net (code "107") (name "unconnected-(JP1-Pad12)") (class "Default")
      (node (ref "JP1") (pin "12") (pinfunction "12_12") (pintype "passive"))
    )
  )
)
